# BatteryBoardV2B.net
KiCad netlist of a schematic drawn in EAGLE
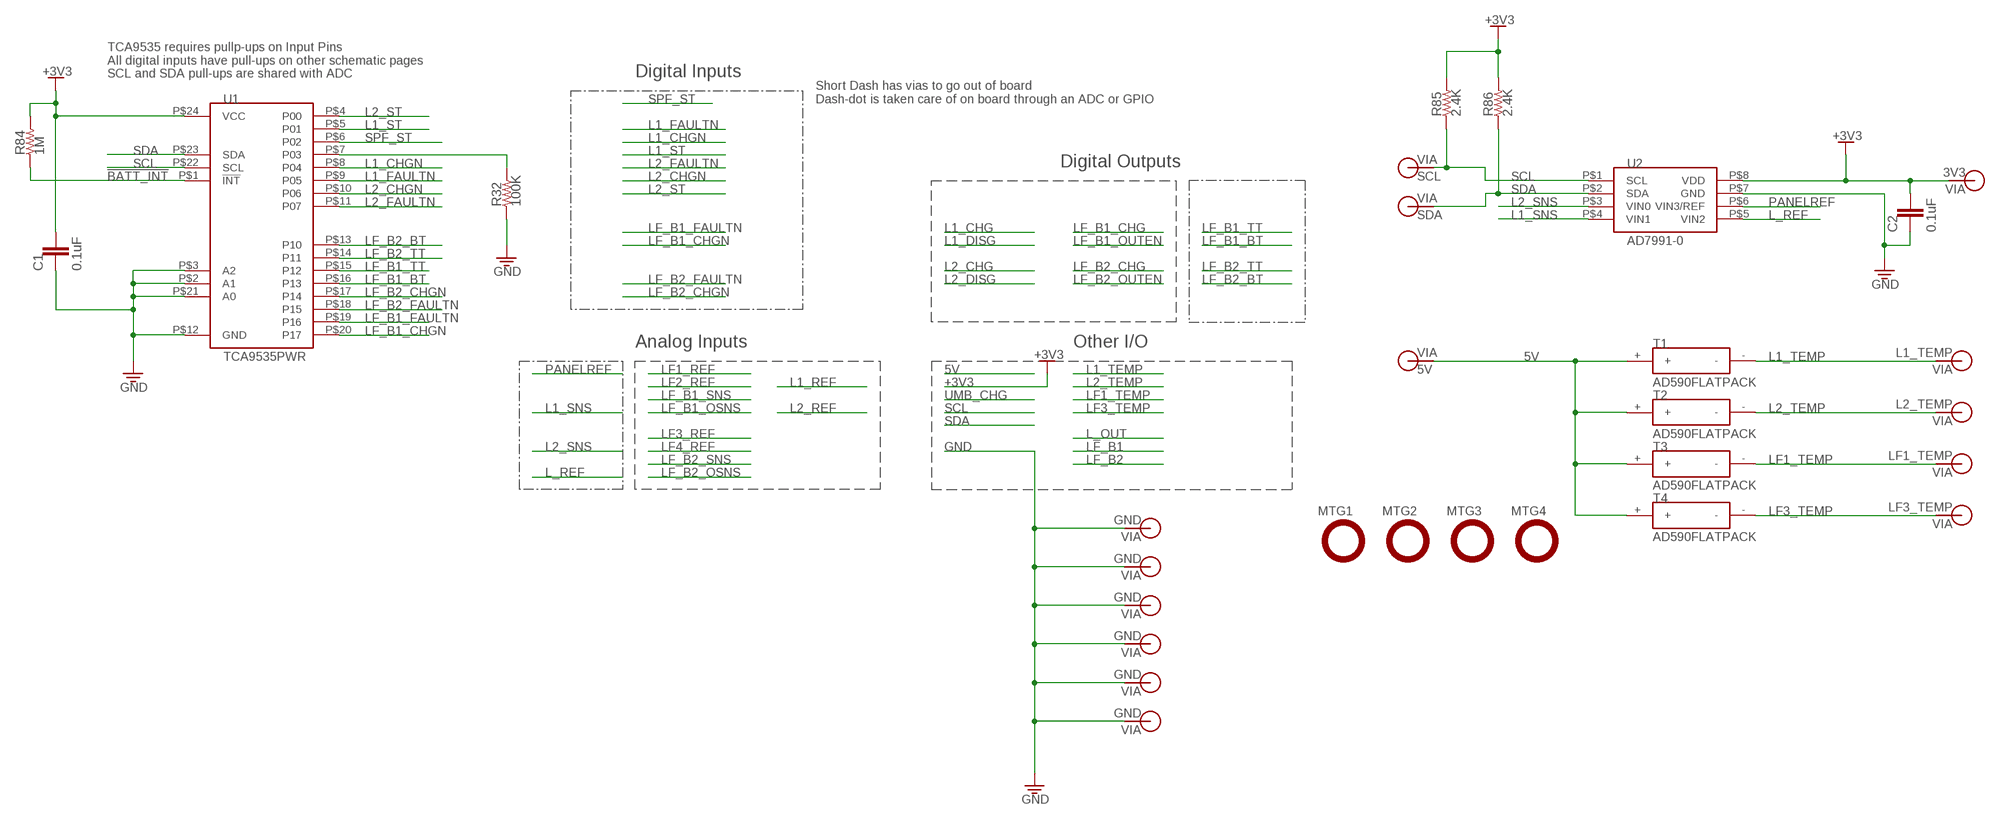
[diagram p0: schematic, sheet 1]
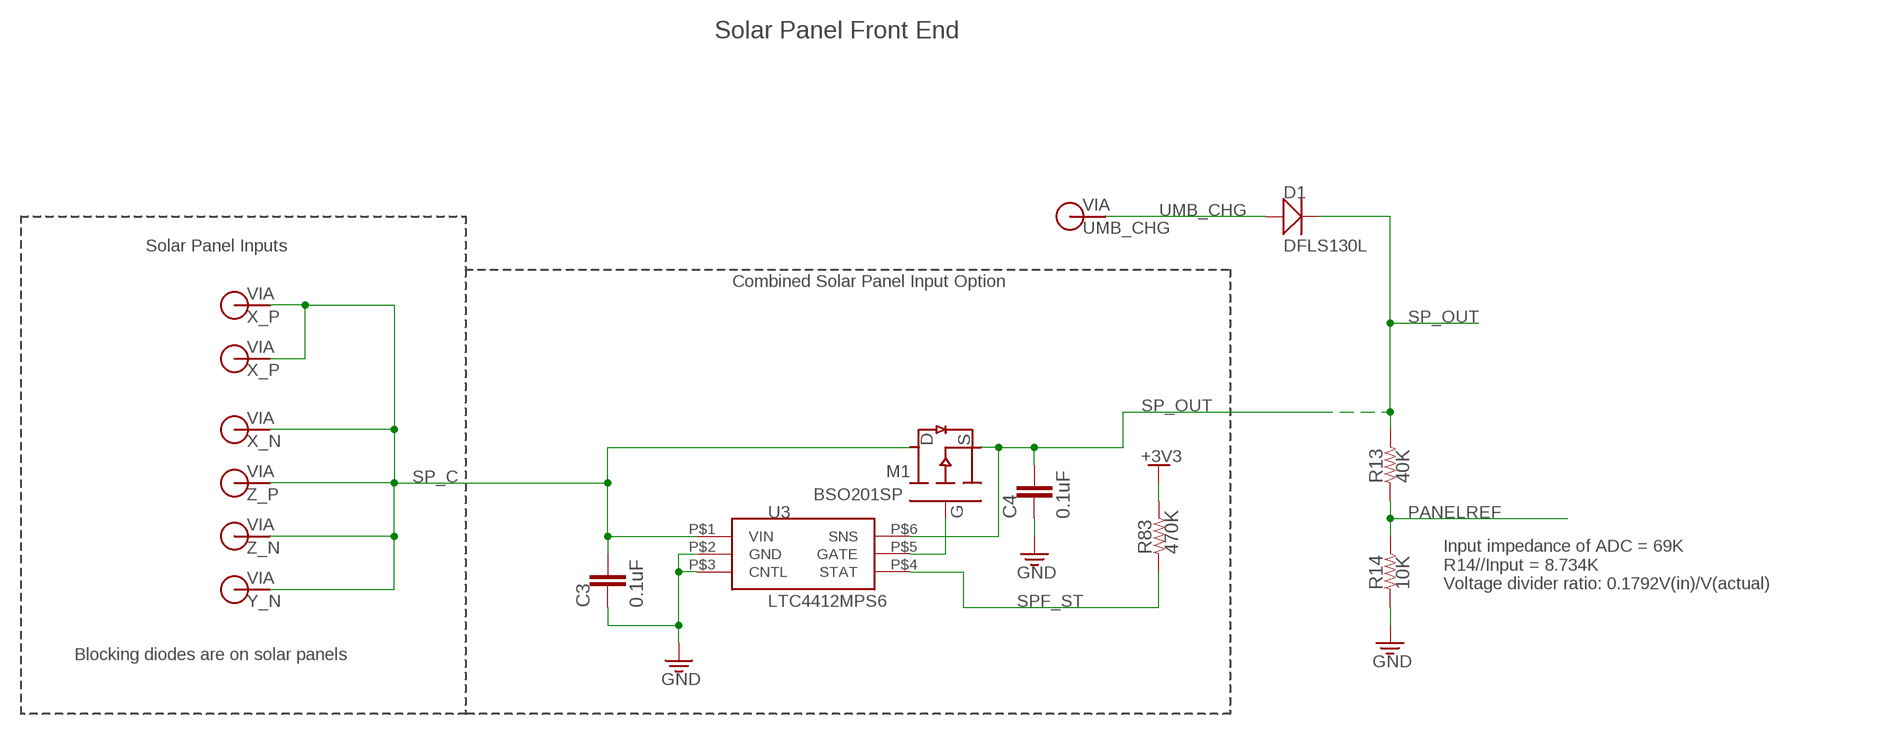
[diagram p1: schematic, sheet 2]
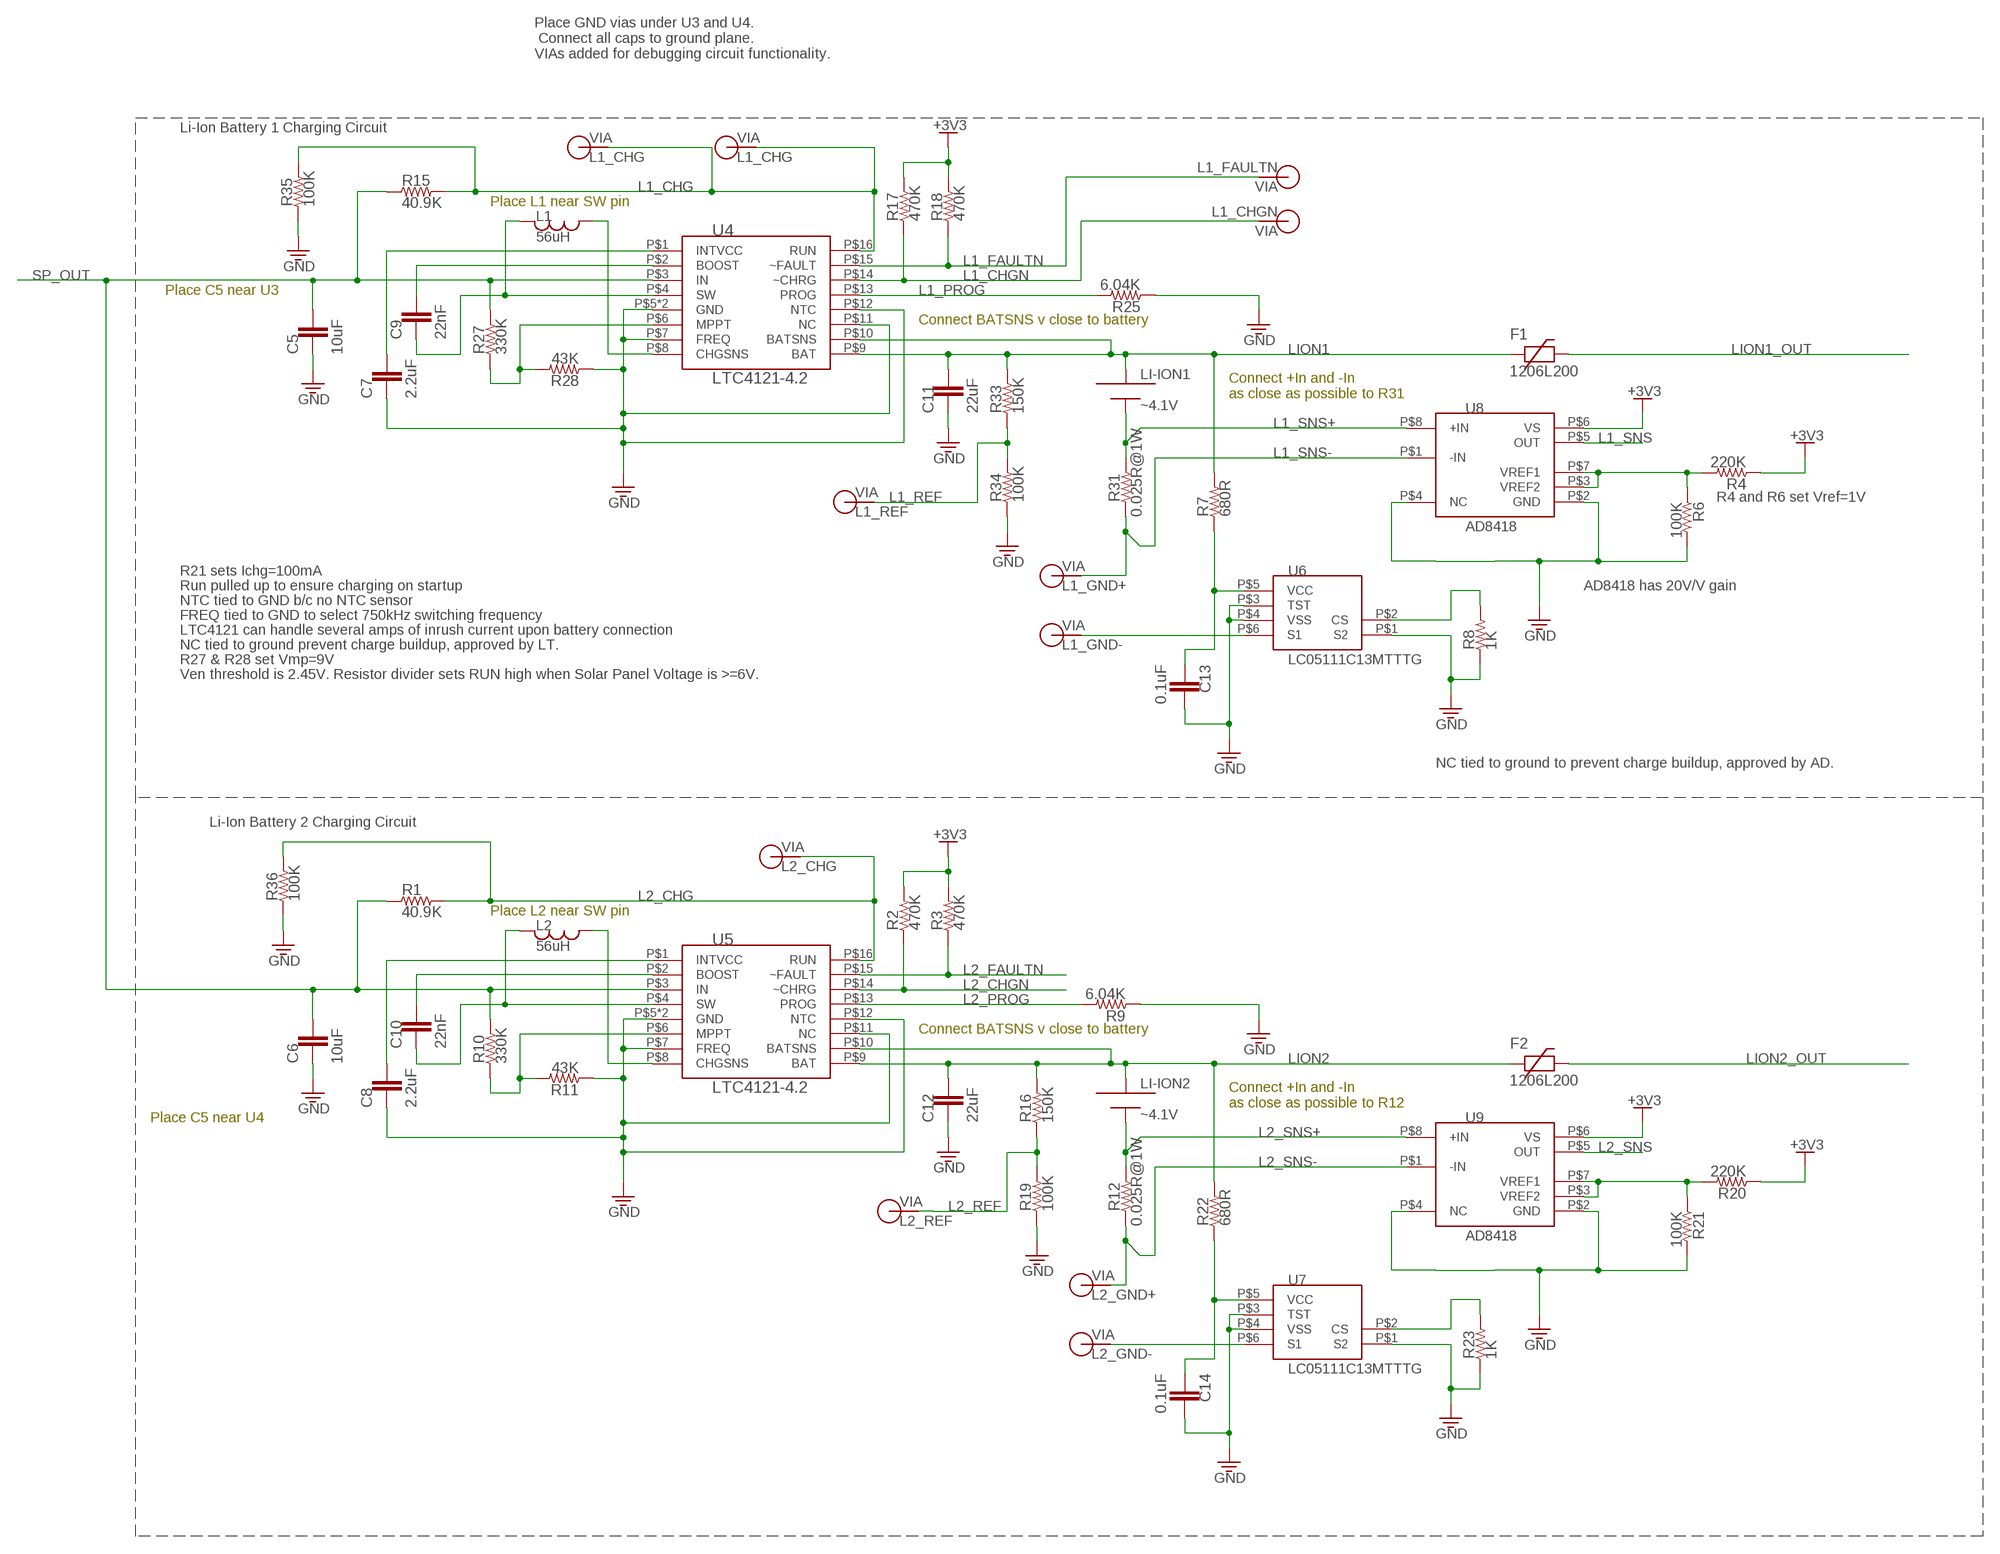
[diagram p2: schematic, sheet 3]
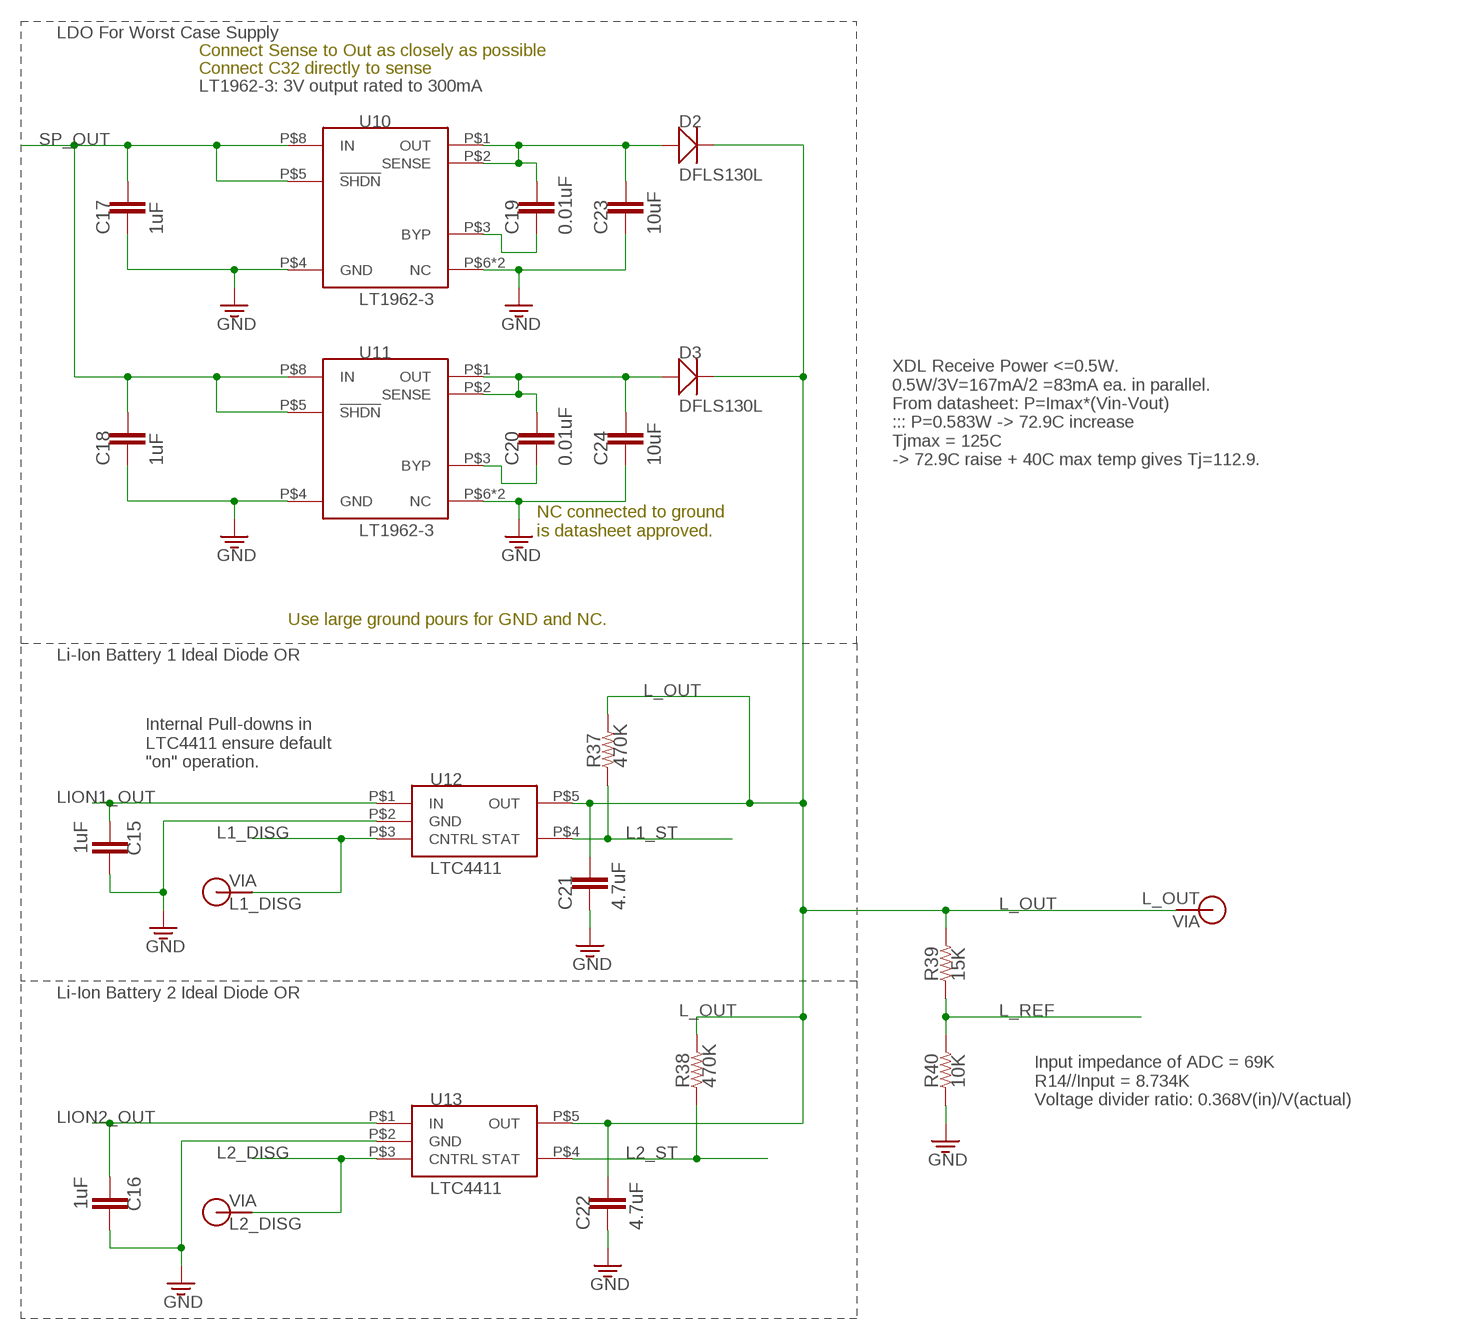
[diagram p3: schematic, sheet 4]
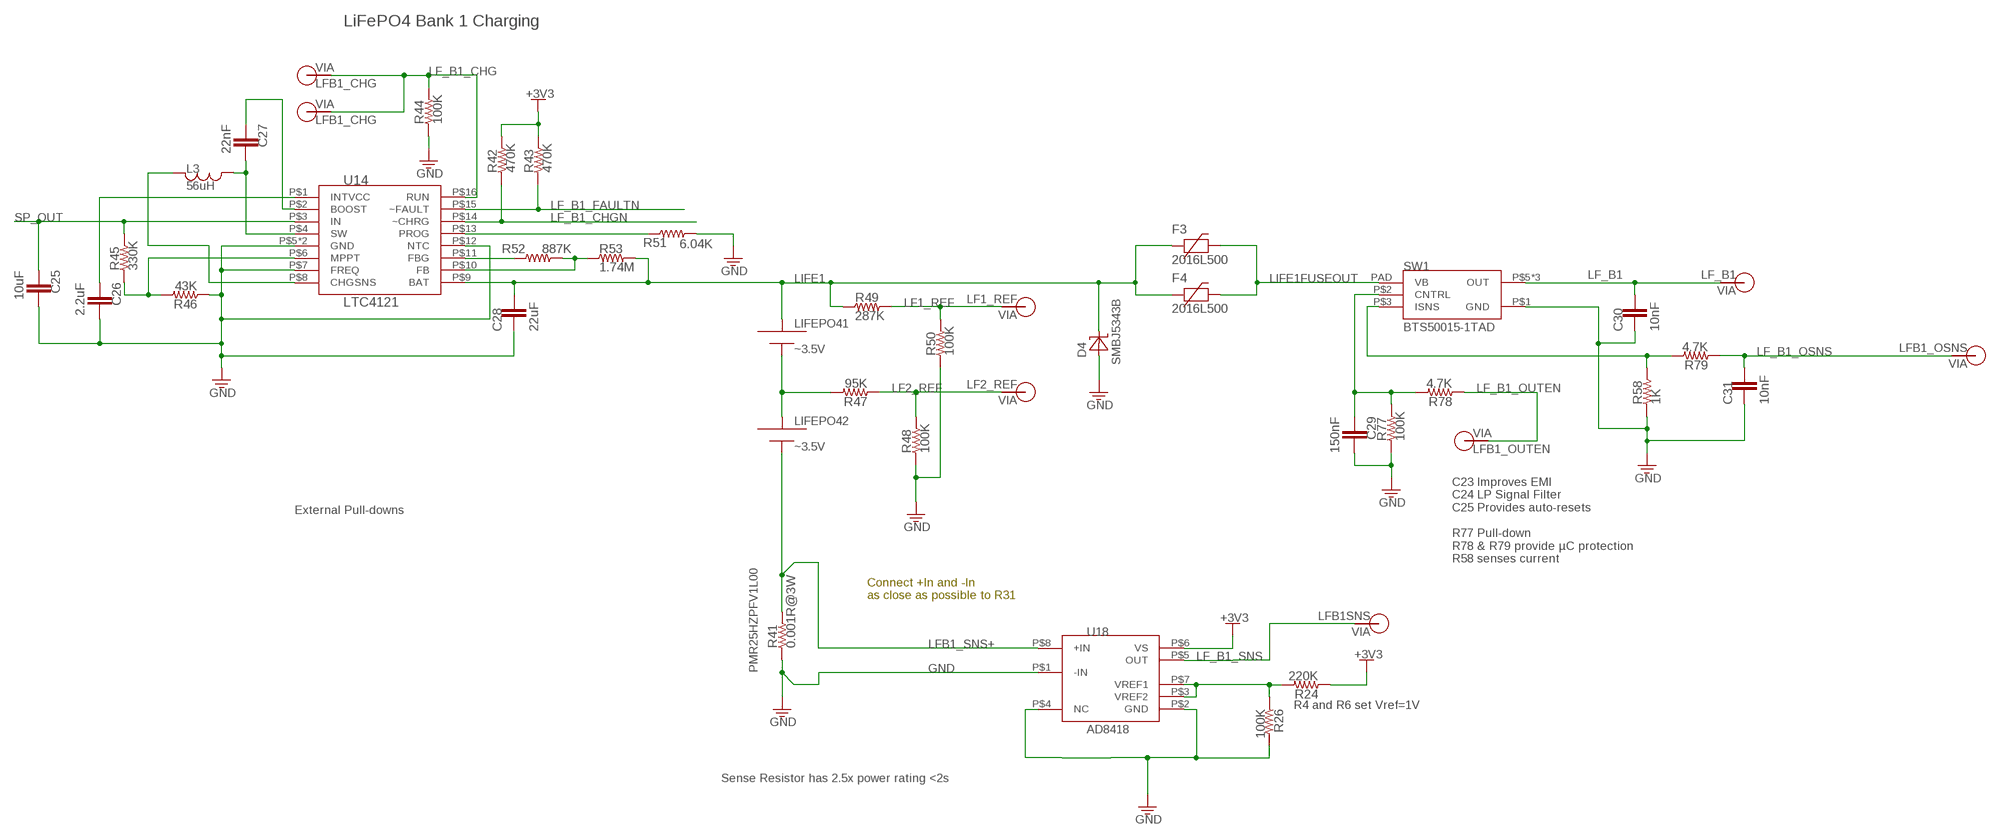
[diagram p4: schematic, sheet 5]
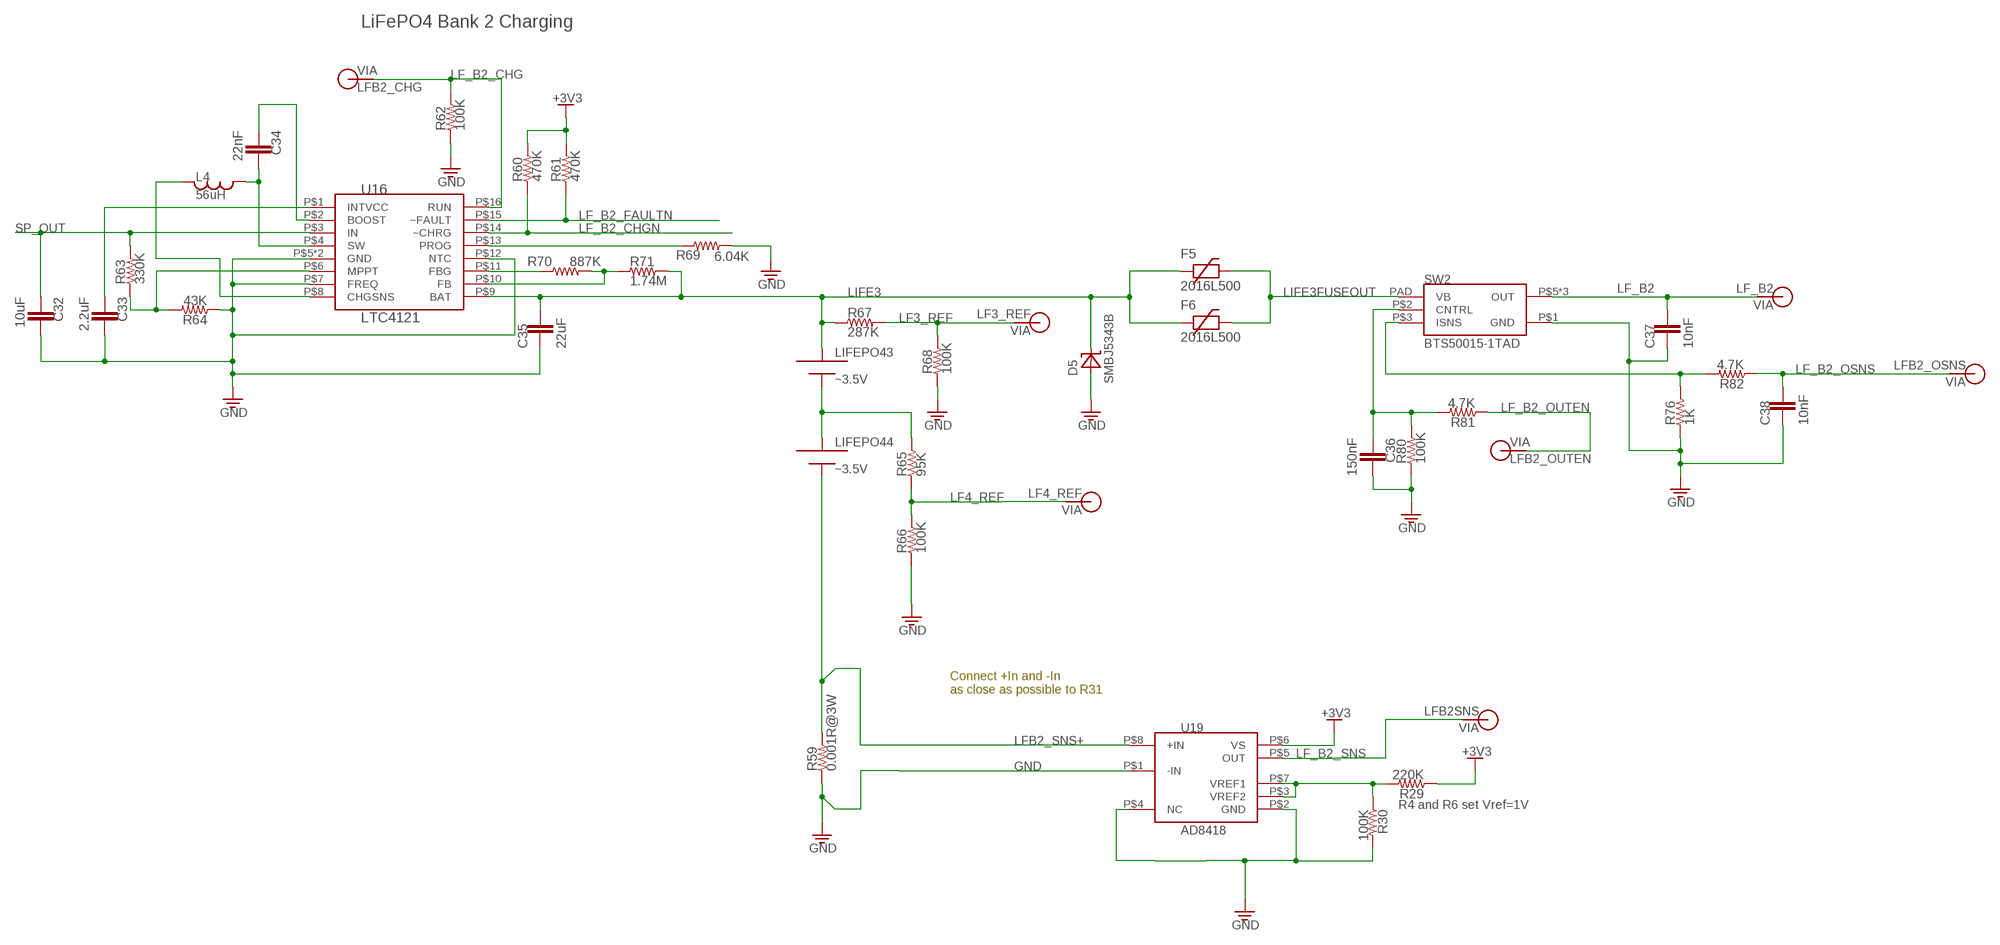
[diagram p5: schematic, sheet 6]

(export (version "E")
  (design (tool "Eeschema 10.0.6"))
  (components
    (comp (ref "C3")
      (value "0.1uF")
      (footprint "eagle-import:0805")
      (libsource (lib "eagle-import") (part "CAP0805"))
    )
    (comp (ref "C4")
      (value "0.1uF")
      (footprint "eagle-import:0805")
      (libsource (lib "eagle-import") (part "CAP0805"))
    )
    (comp (ref "D1")
      (value "DFLS130L")
      (footprint "eagle-import:PWRDI-123")
      (libsource (lib "eagle-import") (part "DFLS130L"))
    )
    (comp (ref "M1")
      (value "BSO201SP")
      (footprint "eagle-import:SO-8")
      (libsource (lib "eagle-import") (part "BSO201SP"))
    )
    (comp (ref "R13")
      (value "40K")
      (footprint "eagle-import:0805")
      (libsource (lib "eagle-import") (part "RES0805"))
    )
    (comp (ref "R14")
      (value "10K")
      (footprint "eagle-import:0805")
      (libsource (lib "eagle-import") (part "RES0805"))
    )
    (comp (ref "R83")
      (value "470K")
      (footprint "eagle-import:0805")
      (libsource (lib "eagle-import") (part "RES0805"))
    )
    (comp (ref "U3")
      (value "LTC4412MPS6")
      (footprint "eagle-import:TSOT23-6")
      (libsource (lib "eagle-import") (part "LTC4412"))
    )
    (comp (ref "V13")
      (value "X_P")
      (footprint "eagle-import:VIA-60MIL")
      (libsource (lib "eagle-import") (part "VIA-60MIL"))
    )
    (comp (ref "V14")
      (value "X_P")
      (footprint "eagle-import:VIA-60MIL-SQ")
      (libsource (lib "eagle-import") (part "VIA60MIL-SQ"))
    )
    (comp (ref "V15")
      (value "X_N")
      (footprint "eagle-import:VIA-60MIL")
      (libsource (lib "eagle-import") (part "VIA-60MIL"))
    )
    (comp (ref "V16")
      (value "Z_P")
      (footprint "eagle-import:VIA-60MIL")
      (libsource (lib "eagle-import") (part "VIA-60MIL"))
    )
    (comp (ref "V17")
      (value "Z_N")
      (footprint "eagle-import:VIA-60MIL")
      (libsource (lib "eagle-import") (part "VIA-60MIL"))
    )
    (comp (ref "V18")
      (value "Y_N")
      (footprint "eagle-import:VIA-60MIL")
      (libsource (lib "eagle-import") (part "VIA-60MIL"))
    )
    (comp (ref "V19")
      (value "UMB_CHG")
      (footprint "eagle-import:VIA-60MIL")
      (libsource (lib "eagle-import") (part "VIA-60MIL"))
    )
    (comp (ref "C25")
      (value "10uF")
      (footprint "eagle-import:0805")
      (libsource (lib "eagle-import") (part "CAP0805"))
    )
    (comp (ref "C26")
      (value "2.2uF")
      (footprint "eagle-import:0805")
      (libsource (lib "eagle-import") (part "CAP0805"))
    )
    (comp (ref "C27")
      (value "22nF")
      (footprint "eagle-import:0805")
      (libsource (lib "eagle-import") (part "CAP0805"))
    )
    (comp (ref "C28")
      (value "22uF")
      (footprint "eagle-import:0805")
      (libsource (lib "eagle-import") (part "CAP0805"))
    )
    (comp (ref "C29")
      (value "150nF")
      (footprint "eagle-import:0805")
      (libsource (lib "eagle-import") (part "CAP0805"))
    )
    (comp (ref "C30")
      (value "10nF")
      (footprint "eagle-import:0805")
      (libsource (lib "eagle-import") (part "CAP0805"))
    )
    (comp (ref "C31")
      (value "10nF")
      (footprint "eagle-import:0805")
      (libsource (lib "eagle-import") (part "CAP0805"))
    )
    (comp (ref "D4")
      (value "SMBJ5343B")
      (footprint "eagle-import:DO214AA")
      (libsource (lib "eagle-import") (part "SMBJ5343B"))
    )
    (comp (ref "F3")
      (value "2016L500")
      (footprint "eagle-import:2016")
      (libsource (lib "eagle-import") (part "2016L500"))
    )
    (comp (ref "F4")
      (value "2016L500")
      (footprint "eagle-import:2016")
      (libsource (lib "eagle-import") (part "2016L500"))
    )
    (comp (ref "L3")
      (value "56uH")
      (footprint "eagle-import:1812")
      (libsource (lib "eagle-import") (part "IND1812"))
    )
    (comp (ref "LIFEPO41")
      (value "~3.5V")
      (footprint "eagle-import:EQUISAT-BATTERY-VA")
      (libsource (lib "eagle-import") (part "LIFEPO4VA"))
    )
    (comp (ref "LIFEPO42")
      (value "~3.5V")
      (footprint "eagle-import:EQUISAT-BATTERY-VB")
      (libsource (lib "eagle-import") (part "LIFEPO4VB"))
    )
    (comp (ref "R24")
      (value "220K")
      (footprint "eagle-import:0805")
      (libsource (lib "eagle-import") (part "RES0805"))
    )
    (comp (ref "R26")
      (value "100K")
      (footprint "eagle-import:0805")
      (libsource (lib "eagle-import") (part "RES0805"))
    )
    (comp (ref "R41")
      (value "0.001R@3W")
      (footprint "eagle-import:1210")
      (libsource (lib "eagle-import") (part "RES1210"))
    )
    (comp (ref "R42")
      (value "470K")
      (footprint "eagle-import:0805")
      (libsource (lib "eagle-import") (part "RES0805"))
    )
    (comp (ref "R43")
      (value "470K")
      (footprint "eagle-import:0805")
      (libsource (lib "eagle-import") (part "RES0805"))
    )
    (comp (ref "R44")
      (value "100K")
      (footprint "eagle-import:0805")
      (libsource (lib "eagle-import") (part "RES0805"))
    )
    (comp (ref "R45")
      (value "330K")
      (footprint "eagle-import:0805")
      (libsource (lib "eagle-import") (part "RES0805"))
    )
    (comp (ref "R46")
      (value "43K")
      (footprint "eagle-import:0805")
      (libsource (lib "eagle-import") (part "RES0805"))
    )
    (comp (ref "R47")
      (value "95K")
      (footprint "eagle-import:0805")
      (libsource (lib "eagle-import") (part "RES0805"))
    )
    (comp (ref "R48")
      (value "100K")
      (footprint "eagle-import:0805")
      (libsource (lib "eagle-import") (part "RES0805"))
    )
    (comp (ref "R49")
      (value "287K")
      (footprint "eagle-import:0805")
      (libsource (lib "eagle-import") (part "RES0805"))
    )
    (comp (ref "R50")
      (value "100K")
      (footprint "eagle-import:0805")
      (libsource (lib "eagle-import") (part "RES0805"))
    )
    (comp (ref "R51")
      (value "6.04K")
      (footprint "eagle-import:0805")
      (libsource (lib "eagle-import") (part "RES0805"))
    )
    (comp (ref "R52")
      (value "887K")
      (footprint "eagle-import:0805")
      (libsource (lib "eagle-import") (part "RES0805"))
    )
    (comp (ref "R53")
      (value "1.74M")
      (footprint "eagle-import:0805")
      (libsource (lib "eagle-import") (part "RES0805"))
    )
    (comp (ref "R58")
      (value "1K")
      (footprint "eagle-import:0805")
      (libsource (lib "eagle-import") (part "RES0805"))
    )
    (comp (ref "R77")
      (value "100K")
      (footprint "eagle-import:0805")
      (libsource (lib "eagle-import") (part "RES0805"))
    )
    (comp (ref "R78")
      (value "4.7K")
      (footprint "eagle-import:0805")
      (libsource (lib "eagle-import") (part "RES0805"))
    )
    (comp (ref "R79")
      (value "4.7K")
      (footprint "eagle-import:0805")
      (libsource (lib "eagle-import") (part "RES0805"))
    )
    (comp (ref "SW1")
      (value "BTS50015-1TAD")
      (footprint "eagle-import:TO-263-7-8")
      (libsource (lib "eagle-import") (part "BTS50015-1TAD"))
    )
    (comp (ref "U14")
      (value "LTC4121")
      (footprint "eagle-import:QFN-16-PAD")
      (libsource (lib "eagle-import") (part "LTC4121"))
    )
    (comp (ref "U18")
      (value "AD8418")
      (footprint "eagle-import:MSOP-8")
      (libsource (lib "eagle-import") (part "AD8418"))
    )
    (comp (ref "V32")
      (value "LFB1_CHG")
      (footprint "eagle-import:VIA-60MIL-SQ")
      (libsource (lib "eagle-import") (part "VIA60MIL-SQ"))
    )
    (comp (ref "V35")
      (value "LFB1_CHG")
      (footprint "eagle-import:VIA-60MIL")
      (libsource (lib "eagle-import") (part "VIA-60MIL"))
    )
    (comp (ref "V40")
      (value "LFB1SNS")
      (footprint "eagle-import:VIA-60MIL")
      (libsource (lib "eagle-import") (part "VIA-60MIL"))
    )
    (comp (ref "V41")
      (value "LF1_REF")
      (footprint "eagle-import:VIA-60MIL")
      (libsource (lib "eagle-import") (part "VIA-60MIL"))
    )
    (comp (ref "V42")
      (value "LF2_REF")
      (footprint "eagle-import:VIA-60MIL")
      (libsource (lib "eagle-import") (part "VIA-60MIL"))
    )
    (comp (ref "V43")
      (value "LFB1_OUTEN")
      (footprint "eagle-import:VIA-60MIL")
      (libsource (lib "eagle-import") (part "VIA-60MIL"))
    )
    (comp (ref "V45")
      (value "LF_B1")
      (footprint "eagle-import:VIA-120MIL")
      (libsource (lib "eagle-import") (part "VIA-120MIL"))
    )
    (comp (ref "V46")
      (value "LFB1_OSNS")
      (footprint "eagle-import:VIA-60MIL")
      (libsource (lib "eagle-import") (part "VIA-60MIL"))
    )
    (comp (ref "C5")
      (value "10uF")
      (footprint "eagle-import:0805")
      (libsource (lib "eagle-import") (part "CAP0805"))
    )
    (comp (ref "C6")
      (value "10uF")
      (footprint "eagle-import:0805")
      (libsource (lib "eagle-import") (part "CAP0805"))
    )
    (comp (ref "C7")
      (value "2.2uF")
      (footprint "eagle-import:0805")
      (libsource (lib "eagle-import") (part "CAP0805"))
    )
    (comp (ref "C8")
      (value "2.2uF")
      (footprint "eagle-import:0805")
      (libsource (lib "eagle-import") (part "CAP0805"))
    )
    (comp (ref "C9")
      (value "22nF")
      (footprint "eagle-import:0805")
      (libsource (lib "eagle-import") (part "CAP0805"))
    )
    (comp (ref "C10")
      (value "22nF")
      (footprint "eagle-import:0805")
      (libsource (lib "eagle-import") (part "CAP0805"))
    )
    (comp (ref "C11")
      (value "22uF")
      (footprint "eagle-import:0805")
      (libsource (lib "eagle-import") (part "CAP0805"))
    )
    (comp (ref "C12")
      (value "22uF")
      (footprint "eagle-import:0805")
      (libsource (lib "eagle-import") (part "CAP0805"))
    )
    (comp (ref "C13")
      (value "0.1uF")
      (footprint "eagle-import:0805")
      (libsource (lib "eagle-import") (part "CAP0805"))
    )
    (comp (ref "C14")
      (value "0.1uF")
      (footprint "eagle-import:0805")
      (libsource (lib "eagle-import") (part "CAP0805"))
    )
    (comp (ref "F1")
      (value "1206L200")
      (footprint "eagle-import:1206")
      (libsource (lib "eagle-import") (part "PTCFUSE1206"))
    )
    (comp (ref "F2")
      (value "1206L200")
      (footprint "eagle-import:1206")
      (libsource (lib "eagle-import") (part "PTCFUSE1206"))
    )
    (comp (ref "L1")
      (value "56uH")
      (footprint "eagle-import:1812")
      (libsource (lib "eagle-import") (part "IND1812"))
    )
    (comp (ref "L2")
      (value "56uH")
      (footprint "eagle-import:1812")
      (libsource (lib "eagle-import") (part "IND1812"))
    )
    (comp (ref "LI-ION1")
      (value "~4.1V")
      (footprint "eagle-import:EQUISAT-BATTERY-VA")
      (libsource (lib "eagle-import") (part "LI-ION"))
    )
    (comp (ref "LI-ION2")
      (value "~4.1V")
      (footprint "eagle-import:EQUISAT-BATTERY-VA")
      (libsource (lib "eagle-import") (part "LI-ION"))
    )
    (comp (ref "R1")
      (value "40.9K")
      (footprint "eagle-import:0805")
      (libsource (lib "eagle-import") (part "RES0805"))
    )
    (comp (ref "R2")
      (value "470K")
      (footprint "eagle-import:0805")
      (libsource (lib "eagle-import") (part "RES0805"))
    )
    (comp (ref "R3")
      (value "470K")
      (footprint "eagle-import:0805")
      (libsource (lib "eagle-import") (part "RES0805"))
    )
    (comp (ref "R4")
      (value "220K")
      (footprint "eagle-import:0805")
      (libsource (lib "eagle-import") (part "RES0805"))
    )
    (comp (ref "R6")
      (value "100K")
      (footprint "eagle-import:0805")
      (libsource (lib "eagle-import") (part "RES0805"))
    )
    (comp (ref "R7")
      (value "680R")
      (footprint "eagle-import:0805")
      (libsource (lib "eagle-import") (part "RES0805"))
    )
    (comp (ref "R8")
      (value "1K")
      (footprint "eagle-import:0805")
      (libsource (lib "eagle-import") (part "RES0805"))
    )
    (comp (ref "R9")
      (value "6.04K")
      (footprint "eagle-import:0805")
      (libsource (lib "eagle-import") (part "RES0805"))
    )
    (comp (ref "R10")
      (value "330K")
      (footprint "eagle-import:0805")
      (libsource (lib "eagle-import") (part "RES0805"))
    )
    (comp (ref "R11")
      (value "43K")
      (footprint "eagle-import:0805")
      (libsource (lib "eagle-import") (part "RES0805"))
    )
    (comp (ref "R12")
      (value "0.025R@1W")
      (footprint "eagle-import:1210")
      (libsource (lib "eagle-import") (part "RES1210"))
    )
    (comp (ref "R15")
      (value "40.9K")
      (footprint "eagle-import:0805")
      (libsource (lib "eagle-import") (part "RES0805"))
    )
    (comp (ref "R16")
      (value "150K")
      (footprint "eagle-import:0805")
      (libsource (lib "eagle-import") (part "RES0805"))
    )
    (comp (ref "R17")
      (value "470K")
      (footprint "eagle-import:0805")
      (libsource (lib "eagle-import") (part "RES0805"))
    )
    (comp (ref "R18")
      (value "470K")
      (footprint "eagle-import:0805")
      (libsource (lib "eagle-import") (part "RES0805"))
    )
    (comp (ref "R19")
      (value "100K")
      (footprint "eagle-import:0805")
      (libsource (lib "eagle-import") (part "RES0805"))
    )
    (comp (ref "R20")
      (value "220K")
      (footprint "eagle-import:0805")
      (libsource (lib "eagle-import") (part "RES0805"))
    )
    (comp (ref "R21")
      (value "100K")
      (footprint "eagle-import:0805")
      (libsource (lib "eagle-import") (part "RES0805"))
    )
    (comp (ref "R22")
      (value "680R")
      (footprint "eagle-import:0805")
      (libsource (lib "eagle-import") (part "RES0805"))
    )
    (comp (ref "R23")
      (value "1K")
      (footprint "eagle-import:0805")
      (libsource (lib "eagle-import") (part "RES0805"))
    )
    (comp (ref "R25")
      (value "6.04K")
      (footprint "eagle-import:0805")
      (libsource (lib "eagle-import") (part "RES0805"))
    )
    (comp (ref "R27")
      (value "330K")
      (footprint "eagle-import:0805")
      (libsource (lib "eagle-import") (part "RES0805"))
    )
    (comp (ref "R28")
      (value "43K")
      (footprint "eagle-import:0805")
      (libsource (lib "eagle-import") (part "RES0805"))
    )
    (comp (ref "R31")
      (value "0.025R@1W")
      (footprint "eagle-import:1210")
      (libsource (lib "eagle-import") (part "RES1210"))
    )
    (comp (ref "R33")
      (value "150K")
      (footprint "eagle-import:0805")
      (libsource (lib "eagle-import") (part "RES0805"))
    )
    (comp (ref "R34")
      (value "100K")
      (footprint "eagle-import:0805")
      (libsource (lib "eagle-import") (part "RES0805"))
    )
    (comp (ref "R35")
      (value "100K")
      (footprint "eagle-import:0805")
      (libsource (lib "eagle-import") (part "RES0805"))
    )
    (comp (ref "R36")
      (value "100K")
      (footprint "eagle-import:0805")
      (libsource (lib "eagle-import") (part "RES0805"))
    )
    (comp (ref "U4")
      (value "LTC4121-4.2")
      (footprint "eagle-import:QFN-16-PAD")
      (libsource (lib "eagle-import") (part "LTC4121-4.2"))
    )
    (comp (ref "U5")
      (value "LTC4121-4.2")
      (footprint "eagle-import:QFN-16-PAD")
      (libsource (lib "eagle-import") (part "LTC4121-4.2"))
    )
    (comp (ref "U6")
      (value "LC05111C13MTTTG")
      (footprint "eagle-import:WDFN6")
      (libsource (lib "eagle-import") (part "LC05111C13MTTTG"))
    )
    (comp (ref "U7")
      (value "LC05111C13MTTTG")
      (footprint "eagle-import:WDFN6")
      (libsource (lib "eagle-import") (part "LC05111C13MTTTG"))
    )
    (comp (ref "U8")
      (value "AD8418")
      (footprint "eagle-import:MSOP-8")
      (libsource (lib "eagle-import") (part "AD8418"))
    )
    (comp (ref "U9")
      (value "AD8418")
      (footprint "eagle-import:MSOP-8")
      (libsource (lib "eagle-import") (part "AD8418"))
    )
    (comp (ref "V20")
      (value "L1_CHG")
      (footprint "eagle-import:VIA-60MIL")
      (libsource (lib "eagle-import") (part "VIA-60MIL"))
    )
    (comp (ref "V21")
      (value "L1_REF")
      (footprint "eagle-import:VIA-60MIL")
      (libsource (lib "eagle-import") (part "VIA-60MIL"))
    )
    (comp (ref "V22")
      (value "L1_GND+")
      (footprint "eagle-import:VIA-60MIL")
      (libsource (lib "eagle-import") (part "VIA-60MIL"))
    )
    (comp (ref "V23")
      (value "L1_GND-")
      (footprint "eagle-import:VIA-60MIL")
      (libsource (lib "eagle-import") (part "VIA-60MIL"))
    )
    (comp (ref "V24")
      (value "L2_GND+")
      (footprint "eagle-import:VIA-60MIL")
      (libsource (lib "eagle-import") (part "VIA-60MIL"))
    )
    (comp (ref "V25")
      (value "L2_GND-")
      (footprint "eagle-import:VIA-60MIL")
      (libsource (lib "eagle-import") (part "VIA-60MIL"))
    )
    (comp (ref "V26")
      (value "L1_FAULTN")
      (footprint "eagle-import:VIA-60MIL-SQ")
      (libsource (lib "eagle-import") (part "VIA60MIL-SQ"))
    )
    (comp (ref "V27")
      (value "L1_CHGN")
      (footprint "eagle-import:VIA-60MIL-SQ")
      (libsource (lib "eagle-import") (part "VIA60MIL-SQ"))
    )
    (comp (ref "V31")
      (value "L2_REF")
      (footprint "eagle-import:VIA-60MIL")
      (libsource (lib "eagle-import") (part "VIA-60MIL"))
    )
    (comp (ref "V33")
      (value "L2_CHG")
      (footprint "eagle-import:VIA-60MIL")
      (libsource (lib "eagle-import") (part "VIA-60MIL"))
    )
    (comp (ref "V48")
      (value "L1_CHG")
      (footprint "eagle-import:VIA-60MIL-SQ")
      (libsource (lib "eagle-import") (part "VIA60MIL-SQ"))
    )
    (comp (ref "C15")
      (value "1uF")
      (footprint "eagle-import:0805")
      (libsource (lib "eagle-import") (part "CAP0805"))
    )
    (comp (ref "C16")
      (value "1uF")
      (footprint "eagle-import:0805")
      (libsource (lib "eagle-import") (part "CAP0805"))
    )
    (comp (ref "C17")
      (value "1uF")
      (footprint "eagle-import:0805")
      (libsource (lib "eagle-import") (part "CAP0805"))
    )
    (comp (ref "C18")
      (value "1uF")
      (footprint "eagle-import:0805")
      (libsource (lib "eagle-import") (part "CAP0805"))
    )
    (comp (ref "C19")
      (value "0.01uF")
      (footprint "eagle-import:0805")
      (libsource (lib "eagle-import") (part "CAP0805"))
    )
    (comp (ref "C20")
      (value "0.01uF")
      (footprint "eagle-import:0805")
      (libsource (lib "eagle-import") (part "CAP0805"))
    )
    (comp (ref "C21")
      (value "4.7uF")
      (footprint "eagle-import:0805")
      (libsource (lib "eagle-import") (part "CAP0805"))
    )
    (comp (ref "C22")
      (value "4.7uF")
      (footprint "eagle-import:0805")
      (libsource (lib "eagle-import") (part "CAP0805"))
    )
    (comp (ref "C23")
      (value "10uF")
      (footprint "eagle-import:0805")
      (libsource (lib "eagle-import") (part "CAP0805"))
    )
    (comp (ref "C24")
      (value "10uF")
      (footprint "eagle-import:0805")
      (libsource (lib "eagle-import") (part "CAP0805"))
    )
    (comp (ref "D2")
      (value "DFLS130L")
      (footprint "eagle-import:PWRDI-123")
      (libsource (lib "eagle-import") (part "DFLS130L"))
    )
    (comp (ref "D3")
      (value "DFLS130L")
      (footprint "eagle-import:PWRDI-123")
      (libsource (lib "eagle-import") (part "DFLS130L"))
    )
    (comp (ref "R37")
      (value "470K")
      (footprint "eagle-import:0805")
      (libsource (lib "eagle-import") (part "RES0805"))
    )
    (comp (ref "R38")
      (value "470K")
      (footprint "eagle-import:0805")
      (libsource (lib "eagle-import") (part "RES0805"))
    )
    (comp (ref "R39")
      (value "15K")
      (footprint "eagle-import:0805")
      (libsource (lib "eagle-import") (part "RES0805"))
    )
    (comp (ref "R40")
      (value "10K")
      (footprint "eagle-import:0805")
      (libsource (lib "eagle-import") (part "RES0805"))
    )
    (comp (ref "U10")
      (value "LT1962-3")
      (footprint "eagle-import:MSOP-8")
      (libsource (lib "eagle-import") (part "LT1962-3"))
    )
    (comp (ref "U11")
      (value "LT1962-3")
      (footprint "eagle-import:MSOP-8")
      (libsource (lib "eagle-import") (part "LT1962-3"))
    )
    (comp (ref "U12")
      (value "LTC4411")
      (footprint "eagle-import:TSOT23-5")
      (libsource (lib "eagle-import") (part "LTC4411"))
    )
    (comp (ref "U13")
      (value "LTC4411")
      (footprint "eagle-import:TSOT23-5")
      (libsource (lib "eagle-import") (part "LTC4411"))
    )
    (comp (ref "V29")
      (value "L1_DISG")
      (footprint "eagle-import:VIA-60MIL")
      (libsource (lib "eagle-import") (part "VIA-60MIL"))
    )
    (comp (ref "V30")
      (value "L2_DISG")
      (footprint "eagle-import:VIA-60MIL")
      (libsource (lib "eagle-import") (part "VIA-60MIL"))
    )
    (comp (ref "V34")
      (value "L_OUT")
      (footprint "eagle-import:VIA-120MIL")
      (libsource (lib "eagle-import") (part "VIA-120MIL"))
    )
    (comp (ref "C32")
      (value "10uF")
      (footprint "eagle-import:0805")
      (libsource (lib "eagle-import") (part "CAP0805"))
    )
    (comp (ref "C33")
      (value "2.2uF")
      (footprint "eagle-import:0805")
      (libsource (lib "eagle-import") (part "CAP0805"))
    )
    (comp (ref "C34")
      (value "22nF")
      (footprint "eagle-import:0805")
      (libsource (lib "eagle-import") (part "CAP0805"))
    )
    (comp (ref "C35")
      (value "22uF")
      (footprint "eagle-import:0805")
      (libsource (lib "eagle-import") (part "CAP0805"))
    )
    (comp (ref "C36")
      (value "150nF")
      (footprint "eagle-import:0805")
      (libsource (lib "eagle-import") (part "CAP0805"))
    )
    (comp (ref "C37")
      (value "10nF")
      (footprint "eagle-import:0805")
      (libsource (lib "eagle-import") (part "CAP0805"))
    )
    (comp (ref "C38")
      (value "10nF")
      (footprint "eagle-import:0805")
      (libsource (lib "eagle-import") (part "CAP0805"))
    )
    (comp (ref "D5")
      (value "SMBJ5343B")
      (footprint "eagle-import:DO214AA")
      (libsource (lib "eagle-import") (part "SMBJ5343B"))
    )
    (comp (ref "F5")
      (value "2016L500")
      (footprint "eagle-import:2016")
      (libsource (lib "eagle-import") (part "2016L500"))
    )
    (comp (ref "F6")
      (value "2016L500")
      (footprint "eagle-import:2016")
      (libsource (lib "eagle-import") (part "2016L500"))
    )
    (comp (ref "L4")
      (value "56uH")
      (footprint "eagle-import:1812")
      (libsource (lib "eagle-import") (part "IND1812"))
    )
    (comp (ref "LIFEPO43")
      (value "~3.5V")
      (footprint "eagle-import:EQUISAT-BATTERY-VA")
      (libsource (lib "eagle-import") (part "LIFEPO4VA"))
    )
    (comp (ref "LIFEPO44")
      (value "~3.5V")
      (footprint "eagle-import:EQUISAT-BATTERY-VB")
      (libsource (lib "eagle-import") (part "LIFEPO4VB"))
    )
    (comp (ref "R29")
      (value "220K")
      (footprint "eagle-import:0805")
      (libsource (lib "eagle-import") (part "RES0805"))
    )
    (comp (ref "R30")
      (value "100K")
      (footprint "eagle-import:0805")
      (libsource (lib "eagle-import") (part "RES0805"))
    )
    (comp (ref "R59")
      (value "0.001R@3W")
      (footprint "eagle-import:1210")
      (libsource (lib "eagle-import") (part "RES1210"))
    )
    (comp (ref "R60")
      (value "470K")
      (footprint "eagle-import:0805")
      (libsource (lib "eagle-import") (part "RES0805"))
    )
    (comp (ref "R61")
      (value "470K")
      (footprint "eagle-import:0805")
      (libsource (lib "eagle-import") (part "RES0805"))
    )
    (comp (ref "R62")
      (value "100K")
      (footprint "eagle-import:0805")
      (libsource (lib "eagle-import") (part "RES0805"))
    )
    (comp (ref "R63")
      (value "330K")
      (footprint "eagle-import:0805")
      (libsource (lib "eagle-import") (part "RES0805"))
    )
    (comp (ref "R64")
      (value "43K")
      (footprint "eagle-import:0805")
      (libsource (lib "eagle-import") (part "RES0805"))
    )
    (comp (ref "R65")
      (value "95K")
      (footprint "eagle-import:0805")
      (libsource (lib "eagle-import") (part "RES0805"))
    )
    (comp (ref "R66")
      (value "100K")
      (footprint "eagle-import:0805")
      (libsource (lib "eagle-import") (part "RES0805"))
    )
    (comp (ref "R67")
      (value "287K")
      (footprint "eagle-import:0805")
      (libsource (lib "eagle-import") (part "RES0805"))
    )
    (comp (ref "R68")
      (value "100K")
      (footprint "eagle-import:0805")
      (libsource (lib "eagle-import") (part "RES0805"))
    )
    (comp (ref "R69")
      (value "6.04K")
      (footprint "eagle-import:0805")
      (libsource (lib "eagle-import") (part "RES0805"))
    )
    (comp (ref "R70")
      (value "887K")
      (footprint "eagle-import:0805")
      (libsource (lib "eagle-import") (part "RES0805"))
    )
    (comp (ref "R71")
      (value "1.74M")
      (footprint "eagle-import:0805")
      (libsource (lib "eagle-import") (part "RES0805"))
    )
    (comp (ref "R76")
      (value "1K")
      (footprint "eagle-import:0805")
      (libsource (lib "eagle-import") (part "RES0805"))
    )
    (comp (ref "R80")
      (value "100K")
      (footprint "eagle-import:0805")
      (libsource (lib "eagle-import") (part "RES0805"))
    )
    (comp (ref "R81")
      (value "4.7K")
      (footprint "eagle-import:0805")
      (libsource (lib "eagle-import") (part "RES0805"))
    )
    (comp (ref "R82")
      (value "4.7K")
      (footprint "eagle-import:0805")
      (libsource (lib "eagle-import") (part "RES0805"))
    )
    (comp (ref "SW2")
      (value "BTS50015-1TAD")
      (footprint "eagle-import:TO-263-7-8")
      (libsource (lib "eagle-import") (part "BTS50015-1TAD"))
    )
    (comp (ref "U16")
      (value "LTC4121")
      (footprint "eagle-import:QFN-16-PAD")
      (libsource (lib "eagle-import") (part "LTC4121"))
    )
    (comp (ref "U19")
      (value "AD8418")
      (footprint "eagle-import:MSOP-8")
      (libsource (lib "eagle-import") (part "AD8418"))
    )
    (comp (ref "V44")
      (value "LFB2SNS")
      (footprint "eagle-import:VIA-60MIL")
      (libsource (lib "eagle-import") (part "VIA-60MIL"))
    )
    (comp (ref "V47")
      (value "LFB2_CHG")
      (footprint "eagle-import:VIA-60MIL")
      (libsource (lib "eagle-import") (part "VIA-60MIL"))
    )
    (comp (ref "V49")
      (value "LF3_REF")
      (footprint "eagle-import:VIA-60MIL")
      (libsource (lib "eagle-import") (part "VIA-60MIL"))
    )
    (comp (ref "V50")
      (value "LF4_REF")
      (footprint "eagle-import:VIA-60MIL")
      (libsource (lib "eagle-import") (part "VIA-60MIL"))
    )
    (comp (ref "V51")
      (value "LFB2_OUTEN")
      (footprint "eagle-import:VIA-60MIL")
      (libsource (lib "eagle-import") (part "VIA-60MIL"))
    )
    (comp (ref "V53")
      (value "LF_B2")
      (footprint "eagle-import:VIA-120MIL")
      (libsource (lib "eagle-import") (part "VIA-120MIL"))
    )
    (comp (ref "V99")
      (value "LFB2_OSNS")
      (footprint "eagle-import:VIA-60MIL")
      (libsource (lib "eagle-import") (part "VIA-60MIL"))
    )
    (comp (ref "C1")
      (value "0.1uF")
      (footprint "eagle-import:0805")
      (libsource (lib "eagle-import") (part "CAP0805"))
    )
    (comp (ref "C2")
      (value "0.1uF")
      (footprint "eagle-import:0805")
      (libsource (lib "eagle-import") (part "CAP0805"))
    )
    (comp (ref "MTG1")
      (value "MTG-NPTH-#2-CLOSE")
      (footprint "eagle-import:#2-CLOSE-NPTH")
      (libsource (lib "eagle-import") (part "MTG-NPTH-#2-CLOSE"))
    )
    (comp (ref "MTG2")
      (value "MTG-NPTH-#2-CLOSE")
      (footprint "eagle-import:#2-CLOSE-NPTH")
      (libsource (lib "eagle-import") (part "MTG-NPTH-#2-CLOSE"))
    )
    (comp (ref "MTG3")
      (value "MTG-NPTH-#2-CLOSE")
      (footprint "eagle-import:#2-CLOSE-NPTH")
      (libsource (lib "eagle-import") (part "MTG-NPTH-#2-CLOSE"))
    )
    (comp (ref "MTG4")
      (value "MTG-NPTH-#2-CLOSE")
      (footprint "eagle-import:#2-CLOSE-NPTH")
      (libsource (lib "eagle-import") (part "MTG-NPTH-#2-CLOSE"))
    )
    (comp (ref "R32")
      (value "100K")
      (footprint "eagle-import:0805")
      (libsource (lib "eagle-import") (part "RES0805"))
    )
    (comp (ref "R84")
      (value "1M")
      (footprint "eagle-import:0805")
      (libsource (lib "eagle-import") (part "RES0805"))
    )
    (comp (ref "R85")
      (value "2.4K")
      (footprint "eagle-import:0805")
      (libsource (lib "eagle-import") (part "RES0805"))
    )
    (comp (ref "R86")
      (value "2.4K")
      (footprint "eagle-import:0805")
      (libsource (lib "eagle-import") (part "RES0805"))
    )
    (comp (ref "T1")
      (value "AD590FLATPACK")
      (footprint "eagle-import:FLATPACK")
      (libsource (lib "eagle-import") (part "AD590FLATPACK"))
    )
    (comp (ref "T2")
      (value "AD590FLATPACK")
      (footprint "eagle-import:FLATPACK")
      (libsource (lib "eagle-import") (part "AD590FLATPACK"))
    )
    (comp (ref "T3")
      (value "AD590FLATPACK")
      (footprint "eagle-import:FLATPACK")
      (libsource (lib "eagle-import") (part "AD590FLATPACK"))
    )
    (comp (ref "T4")
      (value "AD590FLATPACK")
      (footprint "eagle-import:FLATPACK")
      (libsource (lib "eagle-import") (part "AD590FLATPACK"))
    )
    (comp (ref "U1")
      (value "TCA9535PWR")
      (footprint "eagle-import:TSSOP-24")
      (libsource (lib "eagle-import") (part "TCA9535PWR"))
    )
    (comp (ref "U2")
      (value "AD7991-0")
      (footprint "eagle-import:SOT-23-8")
      (libsource (lib "eagle-import") (part "AD7991-0"))
    )
    (comp (ref "V1")
      (value "GND")
      (footprint "eagle-import:VIA-120MIL")
      (libsource (lib "eagle-import") (part "VIA-120MIL"))
    )
    (comp (ref "V2")
      (value "GND")
      (footprint "eagle-import:VIA-120MIL")
      (libsource (lib "eagle-import") (part "VIA-120MIL"))
    )
    (comp (ref "V3")
      (value "GND")
      (footprint "eagle-import:VIA-60MIL-SQ")
      (libsource (lib "eagle-import") (part "VIA60MIL-SQ"))
    )
    (comp (ref "V4")
      (value "GND")
      (footprint "eagle-import:VIA-120MIL")
      (libsource (lib "eagle-import") (part "VIA-120MIL"))
    )
    (comp (ref "V5")
      (value "SCL")
      (footprint "eagle-import:VIA-60MIL")
      (libsource (lib "eagle-import") (part "VIA-60MIL"))
    )
    (comp (ref "V6")
      (value "SDA")
      (footprint "eagle-import:VIA-60MIL")
      (libsource (lib "eagle-import") (part "VIA-60MIL"))
    )
    (comp (ref "V7")
      (value "5V")
      (footprint "eagle-import:VIA-60MIL")
      (libsource (lib "eagle-import") (part "VIA-60MIL"))
    )
    (comp (ref "V8")
      (value "L1_TEMP")
      (footprint "eagle-import:VIA-60MIL")
      (libsource (lib "eagle-import") (part "VIA-60MIL"))
    )
    (comp (ref "V9")
      (value "L2_TEMP")
      (footprint "eagle-import:VIA-60MIL")
      (libsource (lib "eagle-import") (part "VIA-60MIL"))
    )
    (comp (ref "V10")
      (value "LF1_TEMP")
      (footprint "eagle-import:VIA-60MIL")
      (libsource (lib "eagle-import") (part "VIA-60MIL"))
    )
    (comp (ref "V11")
      (value "LF3_TEMP")
      (footprint "eagle-import:VIA-60MIL")
      (libsource (lib "eagle-import") (part "VIA-60MIL"))
    )
    (comp (ref "V12")
      (value "3V3")
      (footprint "eagle-import:VIA-60MIL")
      (libsource (lib "eagle-import") (part "VIA-60MIL"))
    )
    (comp (ref "V28")
      (value "GND")
      (footprint "eagle-import:VIA-60MIL-SQ")
      (libsource (lib "eagle-import") (part "VIA60MIL-SQ"))
    )
    (comp (ref "V36")
      (value "GND")
      (footprint "eagle-import:VIA-60MIL-SQ")
      (libsource (lib "eagle-import") (part "VIA60MIL-SQ"))
    )
  )
  (nets
    (net (code "1") (name "+3V3") (class "Default")
      (node (ref "C1") (pin "1") (pinfunction "P$1_1") (pintype "passive"))
      (node (ref "C2") (pin "1") (pinfunction "P$1_1") (pintype "passive"))
      (node (ref "R17") (pin "2") (pinfunction "2_2") (pintype "passive"))
      (node (ref "R18") (pin "2") (pinfunction "2_2") (pintype "passive"))
      (node (ref "R2") (pin "2") (pinfunction "2_2") (pintype "passive"))
      (node (ref "R20") (pin "1") (pinfunction "1_1") (pintype "passive"))
      (node (ref "R24") (pin "1") (pinfunction "1_1") (pintype "passive"))
      (node (ref "R29") (pin "1") (pinfunction "1_1") (pintype "passive"))
      (node (ref "R3") (pin "2") (pinfunction "2_2") (pintype "passive"))
      (node (ref "R4") (pin "1") (pinfunction "1_1") (pintype "passive"))
      (node (ref "R42") (pin "2") (pinfunction "2_2") (pintype "passive"))
      (node (ref "R43") (pin "2") (pinfunction "2_2") (pintype "passive"))
      (node (ref "R60") (pin "2") (pinfunction "2_2") (pintype "passive"))
      (node (ref "R61") (pin "2") (pinfunction "2_2") (pintype "passive"))
      (node (ref "R83") (pin "2") (pinfunction "2_2") (pintype "passive"))
      (node (ref "R84") (pin "2") (pinfunction "2_2") (pintype "passive"))
      (node (ref "R85") (pin "2") (pinfunction "2_2") (pintype "passive"))
      (node (ref "R86") (pin "2") (pinfunction "2_2") (pintype "passive"))
      (node (ref "U1") (pin "P$24") (pinfunction "VCC_P$24") (pintype "power_in"))
      (node (ref "U18") (pin "P$6") (pinfunction "VS_P$6") (pintype "bidirectional"))
      (node (ref "U19") (pin "P$6") (pinfunction "VS_P$6") (pintype "bidirectional"))
      (node (ref "U2") (pin "P$8") (pinfunction "VDD_P$8") (pintype "bidirectional"))
      (node (ref "U8") (pin "P$6") (pinfunction "VS_P$6") (pintype "bidirectional"))
      (node (ref "U9") (pin "P$6") (pinfunction "VS_P$6") (pintype "bidirectional"))
      (node (ref "V12") (pin "P$1") (pinfunction "P$1_P$1") (pintype "bidirectional"))
    )
    (net (code "2") (name "5V") (class "Default")
      (node (ref "T1") (pin "+") (pinfunction "+_+") (pintype "bidirectional"))
      (node (ref "T2") (pin "+") (pinfunction "+_+") (pintype "bidirectional"))
      (node (ref "T3") (pin "+") (pinfunction "+_+") (pintype "bidirectional"))
      (node (ref "T4") (pin "+") (pinfunction "+_+") (pintype "bidirectional"))
      (node (ref "V7") (pin "P$1") (pinfunction "P$1_P$1") (pintype "bidirectional"))
    )
    (net (code "3") (name "GND") (class "Default")
      (node (ref "C1") (pin "2") (pinfunction "P$2_2") (pintype "passive"))
      (node (ref "C11") (pin "2") (pinfunction "P$2_2") (pintype "passive"))
      (node (ref "C12") (pin "2") (pinfunction "P$2_2") (pintype "passive"))
      (node (ref "C13") (pin "1") (pinfunction "P$1_1") (pintype "passive"))
      (node (ref "C14") (pin "1") (pinfunction "P$1_1") (pintype "passive"))
      (node (ref "C15") (pin "1") (pinfunction "P$1_1") (pintype "passive"))
      (node (ref "C16") (pin "1") (pinfunction "P$1_1") (pintype "passive"))
      (node (ref "C17") (pin "2") (pinfunction "P$2_2") (pintype "passive"))
      (node (ref "C18") (pin "2") (pinfunction "P$2_2") (pintype "passive"))
      (node (ref "C2") (pin "2") (pinfunction "P$2_2") (pintype "passive"))
      (node (ref "C21") (pin "2") (pinfunction "P$2_2") (pintype "passive"))
      (node (ref "C22") (pin "2") (pinfunction "P$2_2") (pintype "passive"))
      (node (ref "C23") (pin "2") (pinfunction "P$2_2") (pintype "passive"))
      (node (ref "C24") (pin "2") (pinfunction "P$2_2") (pintype "passive"))
      (node (ref "C25") (pin "1") (pinfunction "P$1_1") (pintype "passive"))
      (node (ref "C26") (pin "1") (pinfunction "P$1_1") (pintype "passive"))
      (node (ref "C28") (pin "2") (pinfunction "P$2_2") (pintype "passive"))
      (node (ref "C29") (pin "1") (pinfunction "P$1_1") (pintype "passive"))
      (node (ref "C3") (pin "2") (pinfunction "P$2_2") (pintype "passive"))
      (node (ref "C30") (pin "2") (pinfunction "P$2_2") (pintype "passive"))
      (node (ref "C31") (pin "2") (pinfunction "P$2_2") (pintype "passive"))
      (node (ref "C32") (pin "1") (pinfunction "P$1_1") (pintype "passive"))
      (node (ref "C33") (pin "1") (pinfunction "P$1_1") (pintype "passive"))
      (node (ref "C35") (pin "2") (pinfunction "P$2_2") (pintype "passive"))
      (node (ref "C36") (pin "1") (pinfunction "P$1_1") (pintype "passive"))
      (node (ref "C37") (pin "2") (pinfunction "P$2_2") (pintype "passive"))
      (node (ref "C38") (pin "2") (pinfunction "P$2_2") (pintype "passive"))
      (node (ref "C4") (pin "2") (pinfunction "P$2_2") (pintype "passive"))
      (node (ref "C5") (pin "2") (pinfunction "P$2_2") (pintype "passive"))
      (node (ref "C6") (pin "2") (pinfunction "P$2_2") (pintype "passive"))
      (node (ref "C7") (pin "2") (pinfunction "P$2_2") (pintype "passive"))
      (node (ref "C8") (pin "2") (pinfunction "P$2_2") (pintype "passive"))
      (node (ref "D4") (pin "A") (pinfunction "A_A") (pintype "passive"))
      (node (ref "D5") (pin "A") (pinfunction "A_A") (pintype "passive"))
      (node (ref "R11") (pin "1") (pinfunction "1_1") (pintype "passive"))
      (node (ref "R14") (pin "1") (pinfunction "1_1") (pintype "passive"))
      (node (ref "R19") (pin "1") (pinfunction "1_1") (pintype "passive"))
      (node (ref "R21") (pin "2") (pinfunction "2_2") (pintype "passive"))
      (node (ref "R23") (pin "1") (pinfunction "1_1") (pintype "passive"))
      (node (ref "R25") (pin "1") (pinfunction "1_1") (pintype "passive"))
      (node (ref "R26") (pin "2") (pinfunction "2_2") (pintype "passive"))
      (node (ref "R28") (pin "1") (pinfunction "1_1") (pintype "passive"))
      (node (ref "R30") (pin "2") (pinfunction "2_2") (pintype "passive"))
      (node (ref "R32") (pin "1") (pinfunction "1_1") (pintype "passive"))
      (node (ref "R34") (pin "1") (pinfunction "1_1") (pintype "passive"))
      (node (ref "R35") (pin "1") (pinfunction "1_1") (pintype "passive"))
      (node (ref "R36") (pin "1") (pinfunction "1_1") (pintype "passive"))
      (node (ref "R40") (pin "1") (pinfunction "1_1") (pintype "passive"))
      (node (ref "R41") (pin "P$1") (pinfunction "1_P$1") (pintype "passive"))
      (node (ref "R44") (pin "1") (pinfunction "1_1") (pintype "passive"))
      (node (ref "R46") (pin "1") (pinfunction "1_1") (pintype "passive"))
      (node (ref "R48") (pin "1") (pinfunction "1_1") (pintype "passive"))
      (node (ref "R50") (pin "1") (pinfunction "1_1") (pintype "passive"))
      (node (ref "R51") (pin "2") (pinfunction "2_2") (pintype "passive"))
      (node (ref "R58") (pin "1") (pinfunction "1_1") (pintype "passive"))
      (node (ref "R59") (pin "P$1") (pinfunction "1_P$1") (pintype "passive"))
      (node (ref "R6") (pin "2") (pinfunction "2_2") (pintype "passive"))
      (node (ref "R62") (pin "1") (pinfunction "1_1") (pintype "passive"))
      (node (ref "R64") (pin "1") (pinfunction "1_1") (pintype "passive"))
      (node (ref "R66") (pin "1") (pinfunction "1_1") (pintype "passive"))
      (node (ref "R68") (pin "1") (pinfunction "1_1") (pintype "passive"))
      (node (ref "R69") (pin "2") (pinfunction "2_2") (pintype "passive"))
      (node (ref "R76") (pin "1") (pinfunction "1_1") (pintype "passive"))
      (node (ref "R77") (pin "1") (pinfunction "1_1") (pintype "passive"))
      (node (ref "R8") (pin "1") (pinfunction "1_1") (pintype "passive"))
      (node (ref "R80") (pin "1") (pinfunction "1_1") (pintype "passive"))
      (node (ref "R9") (pin "1") (pinfunction "1_1") (pintype "passive"))
      (node (ref "SW1") (pin "P$1") (pinfunction "GND_P$1") (pintype "bidirectional"))
      (node (ref "SW2") (pin "P$1") (pinfunction "GND_P$1") (pintype "bidirectional"))
      (node (ref "U1") (pin "P$12") (pinfunction "GND_P$12") (pintype "power_in"))
      (node (ref "U1") (pin "P$2") (pinfunction "A1_P$2") (pintype "bidirectional"))
      (node (ref "U1") (pin "P$21") (pinfunction "A0_P$21") (pintype "bidirectional"))
      (node (ref "U1") (pin "P$3") (pinfunction "A2_P$3") (pintype "bidirectional"))
      (node (ref "U10") (pin "P$4") (pinfunction "GND_P$4") (pintype "bidirectional"))
      (node (ref "U10") (pin "P$6") (pinfunction "NC_P$6") (pintype "bidirectional"))
      (node (ref "U10") (pin "P$7") (pinfunction "NC_P$7") (pintype "bidirectional"))
      (node (ref "U11") (pin "P$4") (pinfunction "GND_P$4") (pintype "bidirectional"))
      (node (ref "U11") (pin "P$6") (pinfunction "NC_P$6") (pintype "bidirectional"))
      (node (ref "U11") (pin "P$7") (pinfunction "NC_P$7") (pintype "bidirectional"))
      (node (ref "U12") (pin "P$2") (pinfunction "GND_P$2") (pintype "bidirectional"))
      (node (ref "U13") (pin "P$2") (pinfunction "GND_P$2") (pintype "bidirectional"))
      (node (ref "U14") (pin "P$12") (pinfunction "NTC_P$12") (pintype "bidirectional"))
      (node (ref "U14") (pin "P$17") (pinfunction "GND_P$17") (pintype "bidirectional"))
      (node (ref "U14") (pin "P$5") (pinfunction "GND_P$5") (pintype "bidirectional"))
      (node (ref "U14") (pin "P$7") (pinfunction "FREQ_P$7") (pintype "bidirectional"))
      (node (ref "U16") (pin "P$12") (pinfunction "NTC_P$12") (pintype "bidirectional"))
      (node (ref "U16") (pin "P$17") (pinfunction "GND_P$17") (pintype "bidirectional"))
      (node (ref "U16") (pin "P$5") (pinfunction "GND_P$5") (pintype "bidirectional"))
      (node (ref "U16") (pin "P$7") (pinfunction "FREQ_P$7") (pintype "bidirectional"))
      (node (ref "U18") (pin "P$1") (pinfunction "-IN_P$1") (pintype "bidirectional"))
      (node (ref "U18") (pin "P$2") (pinfunction "GND_P$2") (pintype "bidirectional"))
      (node (ref "U18") (pin "P$4") (pinfunction "NC_P$4") (pintype "bidirectional"))
      (node (ref "U19") (pin "P$1") (pinfunction "-IN_P$1") (pintype "bidirectional"))
      (node (ref "U19") (pin "P$2") (pinfunction "GND_P$2") (pintype "bidirectional"))
      (node (ref "U19") (pin "P$4") (pinfunction "NC_P$4") (pintype "bidirectional"))
      (node (ref "U2") (pin "P$7") (pinfunction "GND_P$7") (pintype "bidirectional"))
      (node (ref "U3") (pin "P$2") (pinfunction "GND_P$2") (pintype "bidirectional"))
      (node (ref "U3") (pin "P$3") (pinfunction "CNTL_P$3") (pintype "bidirectional"))
      (node (ref "U4") (pin "P$11") (pinfunction "NC_P$11") (pintype "bidirectional"))
      (node (ref "U4") (pin "P$12") (pinfunction "NTC_P$12") (pintype "bidirectional"))
      (node (ref "U4") (pin "P$17") (pinfunction "GND_P$17") (pintype "bidirectional"))
      (node (ref "U4") (pin "P$5") (pinfunction "GND_P$5") (pintype "bidirectional"))
      (node (ref "U4") (pin "P$7") (pinfunction "FREQ_P$7") (pintype "bidirectional"))
      (node (ref "U5") (pin "P$11") (pinfunction "NC_P$11") (pintype "bidirectional"))
      (node (ref "U5") (pin "P$12") (pinfunction "NTC_P$12") (pintype "bidirectional"))
      (node (ref "U5") (pin "P$17") (pinfunction "GND_P$17") (pintype "bidirectional"))
      (node (ref "U5") (pin "P$5") (pinfunction "GND_P$5") (pintype "bidirectional"))
      (node (ref "U5") (pin "P$7") (pinfunction "FREQ_P$7") (pintype "bidirectional"))
      (node (ref "U6") (pin "P$1") (pinfunction "S2_P$1") (pintype "bidirectional"))
      (node (ref "U6") (pin "P$3") (pinfunction "TST_P$3") (pintype "bidirectional"))
      (node (ref "U6") (pin "P$4") (pinfunction "VSS_P$4") (pintype "bidirectional"))
      (node (ref "U7") (pin "P$1") (pinfunction "S2_P$1") (pintype "bidirectional"))
      (node (ref "U7") (pin "P$3") (pinfunction "TST_P$3") (pintype "bidirectional"))
      (node (ref "U7") (pin "P$4") (pinfunction "VSS_P$4") (pintype "bidirectional"))
      (node (ref "U8") (pin "P$2") (pinfunction "GND_P$2") (pintype "bidirectional"))
      (node (ref "U8") (pin "P$4") (pinfunction "NC_P$4") (pintype "bidirectional"))
      (node (ref "U9") (pin "P$2") (pinfunction "GND_P$2") (pintype "bidirectional"))
      (node (ref "U9") (pin "P$4") (pinfunction "NC_P$4") (pintype "bidirectional"))
      (node (ref "V1") (pin "P$1") (pinfunction "P$1_P$1") (pintype "bidirectional"))
      (node (ref "V2") (pin "P$1") (pinfunction "P$1_P$1") (pintype "bidirectional"))
      (node (ref "V28") (pin "P$1") (pinfunction "P$1_P$1") (pintype "bidirectional"))
      (node (ref "V3") (pin "P$1") (pinfunction "P$1_P$1") (pintype "bidirectional"))
      (node (ref "V36") (pin "P$1") (pinfunction "P$1_P$1") (pintype "bidirectional"))
      (node (ref "V4") (pin "P$1") (pinfunction "P$1_P$1") (pintype "bidirectional"))
    )
    (net (code "4") (name "L1_CHG") (class "Default")
      (node (ref "R15") (pin "2") (pinfunction "2_2") (pintype "passive"))
      (node (ref "R35") (pin "2") (pinfunction "2_2") (pintype "passive"))
      (node (ref "U4") (pin "P$16") (pinfunction "RUN_P$16") (pintype "bidirectional"))
      (node (ref "V20") (pin "P$1") (pinfunction "P$1_P$1") (pintype "bidirectional"))
      (node (ref "V48") (pin "P$1") (pinfunction "P$1_P$1") (pintype "bidirectional"))
    )
    (net (code "5") (name "L1_CHGN") (class "Default")
      (node (ref "R17") (pin "1") (pinfunction "1_1") (pintype "passive"))
      (node (ref "U1") (pin "P$8") (pinfunction "P04_P$8") (pintype "bidirectional"))
      (node (ref "U4") (pin "P$14") (pinfunction "~{CHRG}_P$14") (pintype "bidirectional"))
      (node (ref "V27") (pin "P$1") (pinfunction "P$1_P$1") (pintype "bidirectional"))
    )
    (net (code "6") (name "L1_DISG") (class "Default")
      (node (ref "U12") (pin "P$3") (pinfunction "CNTRL_P$3") (pintype "bidirectional"))
      (node (ref "V29") (pin "P$1") (pinfunction "P$1_P$1") (pintype "bidirectional"))
    )
    (net (code "7") (name "L1_FAULTN") (class "Default")
      (node (ref "R18") (pin "1") (pinfunction "1_1") (pintype "passive"))
      (node (ref "U1") (pin "P$9") (pinfunction "P05_P$9") (pintype "bidirectional"))
      (node (ref "U4") (pin "P$15") (pinfunction "~{FAULT}_P$15") (pintype "bidirectional"))
      (node (ref "V26") (pin "P$1") (pinfunction "P$1_P$1") (pintype "bidirectional"))
    )
    (net (code "8") (name "L1_PROG") (class "Default")
      (node (ref "R25") (pin "2") (pinfunction "2_2") (pintype "passive"))
      (node (ref "U4") (pin "P$13") (pinfunction "PROG_P$13") (pintype "bidirectional"))
    )
    (net (code "9") (name "L1_REF") (class "Default")
      (node (ref "R33") (pin "1") (pinfunction "1_1") (pintype "passive"))
      (node (ref "R34") (pin "2") (pinfunction "2_2") (pintype "passive"))
      (node (ref "V21") (pin "P$1") (pinfunction "P$1_P$1") (pintype "bidirectional"))
    )
    (net (code "10") (name "L1_SNS") (class "Default")
      (node (ref "U2") (pin "P$4") (pinfunction "VIN1_P$4") (pintype "bidirectional"))
      (node (ref "U8") (pin "P$5") (pinfunction "OUT_P$5") (pintype "bidirectional"))
    )
    (net (code "11") (name "L1_SNS+") (class "Default")
      (node (ref "LI-ION1") (pin "MINUS") (pinfunction "MINUS_MINUS") (pintype "power_in"))
      (node (ref "R31") (pin "P$2") (pinfunction "2_P$2") (pintype "passive"))
      (node (ref "U8") (pin "P$8") (pinfunction "+IN_P$8") (pintype "bidirectional"))
    )
    (net (code "12") (name "L1_SNS-") (class "Default")
      (node (ref "R31") (pin "P$1") (pinfunction "1_P$1") (pintype "passive"))
      (node (ref "U8") (pin "P$1") (pinfunction "-IN_P$1") (pintype "bidirectional"))
      (node (ref "V22") (pin "P$1") (pinfunction "P$1_P$1") (pintype "bidirectional"))
    )
    (net (code "13") (name "L1_ST") (class "Default")
      (node (ref "R37") (pin "1") (pinfunction "1_1") (pintype "passive"))
      (node (ref "U1") (pin "P$5") (pinfunction "P01_P$5") (pintype "bidirectional"))
      (node (ref "U12") (pin "P$4") (pinfunction "STAT_P$4") (pintype "bidirectional"))
    )
    (net (code "14") (name "L1_TEMP") (class "Default")
      (node (ref "T1") (pin "-") (pinfunction "-_-") (pintype "bidirectional"))
      (node (ref "V8") (pin "P$1") (pinfunction "P$1_P$1") (pintype "bidirectional"))
    )
    (net (code "15") (name "L2_CHG") (class "Default")
      (node (ref "R1") (pin "2") (pinfunction "2_2") (pintype "passive"))
      (node (ref "R36") (pin "2") (pinfunction "2_2") (pintype "passive"))
      (node (ref "U5") (pin "P$16") (pinfunction "RUN_P$16") (pintype "bidirectional"))
      (node (ref "V33") (pin "P$1") (pinfunction "P$1_P$1") (pintype "bidirectional"))
    )
    (net (code "16") (name "L2_CHGN") (class "Default")
      (node (ref "R2") (pin "1") (pinfunction "1_1") (pintype "passive"))
      (node (ref "U1") (pin "P$10") (pinfunction "P06_P$10") (pintype "bidirectional"))
      (node (ref "U5") (pin "P$14") (pinfunction "~{CHRG}_P$14") (pintype "bidirectional"))
    )
    (net (code "17") (name "L2_DISG") (class "Default")
      (node (ref "U13") (pin "P$3") (pinfunction "CNTRL_P$3") (pintype "bidirectional"))
      (node (ref "V30") (pin "P$1") (pinfunction "P$1_P$1") (pintype "bidirectional"))
    )
    (net (code "18") (name "L2_FAULTN") (class "Default")
      (node (ref "R3") (pin "1") (pinfunction "1_1") (pintype "passive"))
      (node (ref "U1") (pin "P$11") (pinfunction "P07_P$11") (pintype "bidirectional"))
      (node (ref "U5") (pin "P$15") (pinfunction "~{FAULT}_P$15") (pintype "bidirectional"))
    )
    (net (code "19") (name "L2_PROG") (class "Default")
      (node (ref "R9") (pin "2") (pinfunction "2_2") (pintype "passive"))
      (node (ref "U5") (pin "P$13") (pinfunction "PROG_P$13") (pintype "bidirectional"))
    )
    (net (code "20") (name "L2_REF") (class "Default")
      (node (ref "R16") (pin "1") (pinfunction "1_1") (pintype "passive"))
      (node (ref "R19") (pin "2") (pinfunction "2_2") (pintype "passive"))
      (node (ref "V31") (pin "P$1") (pinfunction "P$1_P$1") (pintype "bidirectional"))
    )
    (net (code "21") (name "L2_SNS") (class "Default")
      (node (ref "U2") (pin "P$3") (pinfunction "VIN0_P$3") (pintype "bidirectional"))
      (node (ref "U9") (pin "P$5") (pinfunction "OUT_P$5") (pintype "bidirectional"))
    )
    (net (code "22") (name "L2_SNS+") (class "Default")
      (node (ref "LI-ION2") (pin "MINUS") (pinfunction "MINUS_MINUS") (pintype "power_in"))
      (node (ref "R12") (pin "P$2") (pinfunction "2_P$2") (pintype "passive"))
      (node (ref "U9") (pin "P$8") (pinfunction "+IN_P$8") (pintype "bidirectional"))
    )
    (net (code "23") (name "L2_SNS-") (class "Default")
      (node (ref "R12") (pin "P$1") (pinfunction "1_P$1") (pintype "passive"))
      (node (ref "U9") (pin "P$1") (pinfunction "-IN_P$1") (pintype "bidirectional"))
      (node (ref "V24") (pin "P$1") (pinfunction "P$1_P$1") (pintype "bidirectional"))
    )
    (net (code "24") (name "L2_ST") (class "Default")
      (node (ref "R38") (pin "1") (pinfunction "1_1") (pintype "passive"))
      (node (ref "U1") (pin "P$4") (pinfunction "P00_P$4") (pintype "bidirectional"))
      (node (ref "U13") (pin "P$4") (pinfunction "STAT_P$4") (pintype "bidirectional"))
    )
    (net (code "25") (name "L2_TEMP") (class "Default")
      (node (ref "T2") (pin "-") (pinfunction "-_-") (pintype "bidirectional"))
      (node (ref "V9") (pin "P$1") (pinfunction "P$1_P$1") (pintype "bidirectional"))
    )
    (net (code "26") (name "LF1_REF") (class "Default")
      (node (ref "R49") (pin "2") (pinfunction "2_2") (pintype "passive"))
      (node (ref "R50") (pin "2") (pinfunction "2_2") (pintype "passive"))
      (node (ref "V41") (pin "P$1") (pinfunction "P$1_P$1") (pintype "bidirectional"))
    )
    (net (code "27") (name "LF1_TEMP") (class "Default")
      (node (ref "T3") (pin "-") (pinfunction "-_-") (pintype "bidirectional"))
      (node (ref "V10") (pin "P$1") (pinfunction "P$1_P$1") (pintype "bidirectional"))
    )
    (net (code "28") (name "LF2_REF") (class "Default")
      (node (ref "R47") (pin "1") (pinfunction "1_1") (pintype "passive"))
      (node (ref "R48") (pin "2") (pinfunction "2_2") (pintype "passive"))
      (node (ref "V42") (pin "P$1") (pinfunction "P$1_P$1") (pintype "bidirectional"))
    )
    (net (code "29") (name "LF3_REF") (class "Default")
      (node (ref "R67") (pin "2") (pinfunction "2_2") (pintype "passive"))
      (node (ref "R68") (pin "2") (pinfunction "2_2") (pintype "passive"))
      (node (ref "V49") (pin "P$1") (pinfunction "P$1_P$1") (pintype "bidirectional"))
    )
    (net (code "30") (name "LF3_TEMP") (class "Default")
      (node (ref "T4") (pin "-") (pinfunction "-_-") (pintype "bidirectional"))
      (node (ref "V11") (pin "P$1") (pinfunction "P$1_P$1") (pintype "bidirectional"))
    )
    (net (code "31") (name "LF4_REF") (class "Default")
      (node (ref "R65") (pin "1") (pinfunction "1_1") (pintype "passive"))
      (node (ref "R66") (pin "2") (pinfunction "2_2") (pintype "passive"))
      (node (ref "V50") (pin "P$1") (pinfunction "P$1_P$1") (pintype "bidirectional"))
    )
    (net (code "32") (name "LFB1_SNS+") (class "Default")
      (node (ref "LIFEPO42") (pin "MINUS") (pinfunction "MINUS_MINUS") (pintype "power_in"))
      (node (ref "R41") (pin "P$2") (pinfunction "2_P$2") (pintype "passive"))
      (node (ref "U18") (pin "P$8") (pinfunction "+IN_P$8") (pintype "bidirectional"))
    )
    (net (code "33") (name "LFB2_SNS+") (class "Default")
      (node (ref "LIFEPO44") (pin "MINUS") (pinfunction "MINUS_MINUS") (pintype "power_in"))
      (node (ref "R59") (pin "P$2") (pinfunction "2_P$2") (pintype "passive"))
      (node (ref "U19") (pin "P$8") (pinfunction "+IN_P$8") (pintype "bidirectional"))
    )
    (net (code "34") (name "LF_B1") (class "Default")
      (node (ref "C30") (pin "1") (pinfunction "P$1_1") (pintype "passive"))
      (node (ref "SW1") (pin "P$5") (pinfunction "OUT_P$5") (pintype "power_in"))
      (node (ref "SW1") (pin "P$6") (pinfunction "OUT_P$6") (pintype "power_in"))
      (node (ref "SW1") (pin "P$7") (pinfunction "OUT_P$7") (pintype "power_in"))
      (node (ref "V45") (pin "P$1") (pinfunction "P$1_P$1") (pintype "bidirectional"))
    )
    (net (code "35") (name "LF_B1_BT") (class "Default")
      (node (ref "U1") (pin "P$16") (pinfunction "P13_P$16") (pintype "bidirectional"))
    )
    (net (code "36") (name "LF_B1_CHG") (class "Default")
      (node (ref "R44") (pin "2") (pinfunction "2_2") (pintype "passive"))
      (node (ref "U14") (pin "P$16") (pinfunction "RUN_P$16") (pintype "bidirectional"))
      (node (ref "V32") (pin "P$1") (pinfunction "P$1_P$1") (pintype "bidirectional"))
      (node (ref "V35") (pin "P$1") (pinfunction "P$1_P$1") (pintype "bidirectional"))
    )
    (net (code "37") (name "LF_B1_CHGN") (class "Default")
      (node (ref "R42") (pin "1") (pinfunction "1_1") (pintype "passive"))
      (node (ref "U1") (pin "P$20") (pinfunction "P17_P$20") (pintype "bidirectional"))
      (node (ref "U14") (pin "P$14") (pinfunction "~{CHRG}_P$14") (pintype "bidirectional"))
    )
    (net (code "38") (name "LF_B1_FAULTN") (class "Default")
      (node (ref "R43") (pin "1") (pinfunction "1_1") (pintype "passive"))
      (node (ref "U1") (pin "P$19") (pinfunction "P16_P$19") (pintype "bidirectional"))
      (node (ref "U14") (pin "P$15") (pinfunction "~{FAULT}_P$15") (pintype "bidirectional"))
    )
    (net (code "39") (name "LF_B1_OSNS") (class "Default")
      (node (ref "C31") (pin "1") (pinfunction "P$1_1") (pintype "passive"))
      (node (ref "R79") (pin "1") (pinfunction "1_1") (pintype "passive"))
      (node (ref "V46") (pin "P$1") (pinfunction "P$1_P$1") (pintype "bidirectional"))
    )
    (net (code "40") (name "LF_B1_OUTEN") (class "Default")
      (node (ref "R78") (pin "1") (pinfunction "1_1") (pintype "passive"))
      (node (ref "V43") (pin "P$1") (pinfunction "P$1_P$1") (pintype "bidirectional"))
    )
    (net (code "41") (name "LF_B1_SNS") (class "Default")
      (node (ref "U18") (pin "P$5") (pinfunction "OUT_P$5") (pintype "bidirectional"))
      (node (ref "V40") (pin "P$1") (pinfunction "P$1_P$1") (pintype "bidirectional"))
    )
    (net (code "42") (name "LF_B1_TT") (class "Default")
      (node (ref "U1") (pin "P$15") (pinfunction "P12_P$15") (pintype "bidirectional"))
    )
    (net (code "43") (name "LF_B2") (class "Default")
      (node (ref "C37") (pin "1") (pinfunction "P$1_1") (pintype "passive"))
      (node (ref "SW2") (pin "P$5") (pinfunction "OUT_P$5") (pintype "power_in"))
      (node (ref "SW2") (pin "P$6") (pinfunction "OUT_P$6") (pintype "power_in"))
      (node (ref "SW2") (pin "P$7") (pinfunction "OUT_P$7") (pintype "power_in"))
      (node (ref "V53") (pin "P$1") (pinfunction "P$1_P$1") (pintype "bidirectional"))
    )
    (net (code "44") (name "LF_B2_BT") (class "Default")
      (node (ref "U1") (pin "P$13") (pinfunction "P10_P$13") (pintype "bidirectional"))
    )
    (net (code "45") (name "LF_B2_CHG") (class "Default")
      (node (ref "R62") (pin "2") (pinfunction "2_2") (pintype "passive"))
      (node (ref "U16") (pin "P$16") (pinfunction "RUN_P$16") (pintype "bidirectional"))
      (node (ref "V47") (pin "P$1") (pinfunction "P$1_P$1") (pintype "bidirectional"))
    )
    (net (code "46") (name "LF_B2_CHGN") (class "Default")
      (node (ref "R60") (pin "1") (pinfunction "1_1") (pintype "passive"))
      (node (ref "U1") (pin "P$17") (pinfunction "P14_P$17") (pintype "bidirectional"))
      (node (ref "U16") (pin "P$14") (pinfunction "~{CHRG}_P$14") (pintype "bidirectional"))
    )
    (net (code "47") (name "LF_B2_FAULTN") (class "Default")
      (node (ref "R61") (pin "1") (pinfunction "1_1") (pintype "passive"))
      (node (ref "U1") (pin "P$18") (pinfunction "P15_P$18") (pintype "bidirectional"))
      (node (ref "U16") (pin "P$15") (pinfunction "~{FAULT}_P$15") (pintype "bidirectional"))
    )
    (net (code "48") (name "LF_B2_OSNS") (class "Default")
      (node (ref "C38") (pin "1") (pinfunction "P$1_1") (pintype "passive"))
      (node (ref "R82") (pin "1") (pinfunction "1_1") (pintype "passive"))
      (node (ref "V99") (pin "P$1") (pinfunction "P$1_P$1") (pintype "bidirectional"))
    )
    (net (code "49") (name "LF_B2_OUTEN") (class "Default")
      (node (ref "R81") (pin "1") (pinfunction "1_1") (pintype "passive"))
      (node (ref "V51") (pin "P$1") (pinfunction "P$1_P$1") (pintype "bidirectional"))
    )
    (net (code "50") (name "LF_B2_SNS") (class "Default")
      (node (ref "U19") (pin "P$5") (pinfunction "OUT_P$5") (pintype "bidirectional"))
      (node (ref "V44") (pin "P$1") (pinfunction "P$1_P$1") (pintype "bidirectional"))
    )
    (net (code "51") (name "LF_B2_TT") (class "Default")
      (node (ref "U1") (pin "P$14") (pinfunction "P11_P$14") (pintype "bidirectional"))
    )
    (net (code "52") (name "LIFE1") (class "Default")
      (node (ref "C28") (pin "1") (pinfunction "P$1_1") (pintype "passive"))
      (node (ref "D4") (pin "C") (pinfunction "C_C") (pintype "passive"))
      (node (ref "F3") (pin "P$1") (pinfunction "P$1_P$1") (pintype "passive"))
      (node (ref "F4") (pin "P$1") (pinfunction "P$1_P$1") (pintype "passive"))
      (node (ref "LIFEPO41") (pin "PLUS") (pinfunction "PLUS_PLUS") (pintype "power_in"))
      (node (ref "R49") (pin "1") (pinfunction "1_1") (pintype "passive"))
      (node (ref "R53") (pin "2") (pinfunction "2_2") (pintype "passive"))
      (node (ref "U14") (pin "P$9") (pinfunction "BAT_P$9") (pintype "bidirectional"))
    )
    (net (code "53") (name "LIFE1FUSEOUT") (class "Default")
      (node (ref "F3") (pin "P$2") (pinfunction "P$2_P$2") (pintype "passive"))
      (node (ref "F4") (pin "P$2") (pinfunction "P$2_P$2") (pintype "passive"))
      (node (ref "SW1") (pin "PAD") (pinfunction "VB_PAD") (pintype "power_in"))
    )
    (net (code "54") (name "LIFE3") (class "Default")
      (node (ref "C35") (pin "1") (pinfunction "P$1_1") (pintype "passive"))
      (node (ref "D5") (pin "C") (pinfunction "C_C") (pintype "passive"))
      (node (ref "F5") (pin "P$1") (pinfunction "P$1_P$1") (pintype "passive"))
      (node (ref "F6") (pin "P$1") (pinfunction "P$1_P$1") (pintype "passive"))
      (node (ref "LIFEPO43") (pin "PLUS") (pinfunction "PLUS_PLUS") (pintype "power_in"))
      (node (ref "R67") (pin "1") (pinfunction "1_1") (pintype "passive"))
      (node (ref "R71") (pin "2") (pinfunction "2_2") (pintype "passive"))
      (node (ref "U16") (pin "P$9") (pinfunction "BAT_P$9") (pintype "bidirectional"))
    )
    (net (code "55") (name "LIFE3FUSEOUT") (class "Default")
      (node (ref "F5") (pin "P$2") (pinfunction "P$2_P$2") (pintype "passive"))
      (node (ref "F6") (pin "P$2") (pinfunction "P$2_P$2") (pintype "passive"))
      (node (ref "SW2") (pin "PAD") (pinfunction "VB_PAD") (pintype "power_in"))
    )
    (net (code "56") (name "LION1") (class "Default")
      (node (ref "C11") (pin "1") (pinfunction "P$1_1") (pintype "passive"))
      (node (ref "F1") (pin "1") (pinfunction "P$1_1") (pintype "passive"))
      (node (ref "LI-ION1") (pin "PLUS") (pinfunction "PLUS_PLUS") (pintype "power_in"))
      (node (ref "R33") (pin "2") (pinfunction "2_2") (pintype "passive"))
      (node (ref "R7") (pin "2") (pinfunction "2_2") (pintype "passive"))
      (node (ref "U4") (pin "P$10") (pinfunction "BATSNS_P$10") (pintype "bidirectional"))
      (node (ref "U4") (pin "P$9") (pinfunction "BAT_P$9") (pintype "bidirectional"))
    )
    (net (code "57") (name "LION1_OUT") (class "Default")
      (node (ref "C15") (pin "2") (pinfunction "P$2_2") (pintype "passive"))
      (node (ref "F1") (pin "2") (pinfunction "P$2_2") (pintype "passive"))
      (node (ref "U12") (pin "P$1") (pinfunction "IN_P$1") (pintype "bidirectional"))
    )
    (net (code "58") (name "LION2") (class "Default")
      (node (ref "C12") (pin "1") (pinfunction "P$1_1") (pintype "passive"))
      (node (ref "F2") (pin "1") (pinfunction "P$1_1") (pintype "passive"))
      (node (ref "LI-ION2") (pin "PLUS") (pinfunction "PLUS_PLUS") (pintype "power_in"))
      (node (ref "R16") (pin "2") (pinfunction "2_2") (pintype "passive"))
      (node (ref "R22") (pin "2") (pinfunction "2_2") (pintype "passive"))
      (node (ref "U5") (pin "P$10") (pinfunction "BATSNS_P$10") (pintype "bidirectional"))
      (node (ref "U5") (pin "P$9") (pinfunction "BAT_P$9") (pintype "bidirectional"))
    )
    (net (code "59") (name "LION2_OUT") (class "Default")
      (node (ref "C16") (pin "2") (pinfunction "P$2_2") (pintype "passive"))
      (node (ref "F2") (pin "2") (pinfunction "P$2_2") (pintype "passive"))
      (node (ref "U13") (pin "P$1") (pinfunction "IN_P$1") (pintype "bidirectional"))
    )
    (net (code "60") (name "L_OUT") (class "Default")
      (node (ref "C21") (pin "1") (pinfunction "P$1_1") (pintype "passive"))
      (node (ref "C22") (pin "1") (pinfunction "P$1_1") (pintype "passive"))
      (node (ref "D2") (pin "C") (pinfunction "C_C") (pintype "bidirectional"))
      (node (ref "D3") (pin "C") (pinfunction "C_C") (pintype "bidirectional"))
      (node (ref "R37") (pin "2") (pinfunction "2_2") (pintype "passive"))
      (node (ref "R38") (pin "2") (pinfunction "2_2") (pintype "passive"))
      (node (ref "R39") (pin "2") (pinfunction "2_2") (pintype "passive"))
      (node (ref "U12") (pin "P$5") (pinfunction "OUT_P$5") (pintype "bidirectional"))
      (node (ref "U13") (pin "P$5") (pinfunction "OUT_P$5") (pintype "bidirectional"))
      (node (ref "V34") (pin "P$1") (pinfunction "P$1_P$1") (pintype "bidirectional"))
    )
    (net (code "61") (name "L_REF") (class "Default")
      (node (ref "R39") (pin "1") (pinfunction "1_1") (pintype "passive"))
      (node (ref "R40") (pin "2") (pinfunction "2_2") (pintype "passive"))
      (node (ref "U2") (pin "P$5") (pinfunction "VIN2_P$5") (pintype "bidirectional"))
    )
    (net (code "62") (name "Net-(C7-P$1)") (class "Default")
      (node (ref "C7") (pin "1") (pinfunction "P$1_1") (pintype "passive"))
      (node (ref "U4") (pin "P$1") (pinfunction "INTVCC_P$1") (pintype "bidirectional"))
    )
    (net (code "63") (name "Net-(C8-P$1)") (class "Default")
      (node (ref "C8") (pin "1") (pinfunction "P$1_1") (pintype "passive"))
      (node (ref "U5") (pin "P$1") (pinfunction "INTVCC_P$1") (pintype "bidirectional"))
    )
    (net (code "64") (name "Net-(C9-P$1)") (class "Default")
      (node (ref "C9") (pin "1") (pinfunction "P$1_1") (pintype "passive"))
      (node (ref "U4") (pin "P$2") (pinfunction "BOOST_P$2") (pintype "bidirectional"))
    )
    (net (code "65") (name "Net-(C9-P$2)") (class "Default")
      (node (ref "C9") (pin "2") (pinfunction "P$2_2") (pintype "passive"))
      (node (ref "L1") (pin "P$1") (pinfunction "P$1_P$1") (pintype "passive"))
      (node (ref "U4") (pin "P$4") (pinfunction "SW_P$4") (pintype "bidirectional"))
    )
    (net (code "66") (name "Net-(C10-P$1)") (class "Default")
      (node (ref "C10") (pin "1") (pinfunction "P$1_1") (pintype "passive"))
      (node (ref "U5") (pin "P$2") (pinfunction "BOOST_P$2") (pintype "bidirectional"))
    )
    (net (code "67") (name "Net-(C10-P$2)") (class "Default")
      (node (ref "C10") (pin "2") (pinfunction "P$2_2") (pintype "passive"))
      (node (ref "L2") (pin "P$1") (pinfunction "P$1_P$1") (pintype "passive"))
      (node (ref "U5") (pin "P$4") (pinfunction "SW_P$4") (pintype "bidirectional"))
    )
    (net (code "68") (name "Net-(C13-P$2)") (class "Default")
      (node (ref "C13") (pin "2") (pinfunction "P$2_2") (pintype "passive"))
      (node (ref "R7") (pin "1") (pinfunction "1_1") (pintype "passive"))
      (node (ref "U6") (pin "P$5") (pinfunction "VCC_P$5") (pintype "bidirectional"))
    )
    (net (code "69") (name "Net-(C14-P$2)") (class "Default")
      (node (ref "C14") (pin "2") (pinfunction "P$2_2") (pintype "passive"))
      (node (ref "R22") (pin "1") (pinfunction "1_1") (pintype "passive"))
      (node (ref "U7") (pin "P$5") (pinfunction "VCC_P$5") (pintype "bidirectional"))
    )
    (net (code "70") (name "Net-(C19-P$1)") (class "Default")
      (node (ref "C19") (pin "1") (pinfunction "P$1_1") (pintype "passive"))
      (node (ref "C23") (pin "1") (pinfunction "P$1_1") (pintype "passive"))
      (node (ref "D2") (pin "A") (pinfunction "A_A") (pintype "bidirectional"))
      (node (ref "U10") (pin "P$1") (pinfunction "OUT_P$1") (pintype "bidirectional"))
      (node (ref "U10") (pin "P$2") (pinfunction "SENSE_P$2") (pintype "bidirectional"))
    )
    (net (code "71") (name "Net-(C19-P$2)") (class "Default")
      (node (ref "C19") (pin "2") (pinfunction "P$2_2") (pintype "passive"))
      (node (ref "U10") (pin "P$3") (pinfunction "BYP_P$3") (pintype "bidirectional"))
    )
    (net (code "72") (name "Net-(C20-P$1)") (class "Default")
      (node (ref "C20") (pin "1") (pinfunction "P$1_1") (pintype "passive"))
      (node (ref "C24") (pin "1") (pinfunction "P$1_1") (pintype "passive"))
      (node (ref "D3") (pin "A") (pinfunction "A_A") (pintype "bidirectional"))
      (node (ref "U11") (pin "P$1") (pinfunction "OUT_P$1") (pintype "bidirectional"))
      (node (ref "U11") (pin "P$2") (pinfunction "SENSE_P$2") (pintype "bidirectional"))
    )
    (net (code "73") (name "Net-(C20-P$2)") (class "Default")
      (node (ref "C20") (pin "2") (pinfunction "P$2_2") (pintype "passive"))
      (node (ref "U11") (pin "P$3") (pinfunction "BYP_P$3") (pintype "bidirectional"))
    )
    (net (code "74") (name "Net-(C26-P$2)") (class "Default")
      (node (ref "C26") (pin "2") (pinfunction "P$2_2") (pintype "passive"))
      (node (ref "U14") (pin "P$1") (pinfunction "INTVCC_P$1") (pintype "bidirectional"))
    )
    (net (code "75") (name "Net-(C27-P$1)") (class "Default")
      (node (ref "C27") (pin "1") (pinfunction "P$1_1") (pintype "passive"))
      (node (ref "L3") (pin "P$2") (pinfunction "P$2_P$2") (pintype "passive"))
      (node (ref "U14") (pin "P$4") (pinfunction "SW_P$4") (pintype "bidirectional"))
    )
    (net (code "76") (name "Net-(C27-P$2)") (class "Default")
      (node (ref "C27") (pin "2") (pinfunction "P$2_2") (pintype "passive"))
      (node (ref "U14") (pin "P$2") (pinfunction "BOOST_P$2") (pintype "bidirectional"))
    )
    (net (code "77") (name "Net-(C29-P$2)") (class "Default")
      (node (ref "C29") (pin "2") (pinfunction "P$2_2") (pintype "passive"))
      (node (ref "R77") (pin "2") (pinfunction "2_2") (pintype "passive"))
      (node (ref "R78") (pin "2") (pinfunction "2_2") (pintype "passive"))
      (node (ref "SW1") (pin "P$2") (pinfunction "CNTRL_P$2") (pintype "input"))
    )
    (net (code "78") (name "Net-(C33-P$2)") (class "Default")
      (node (ref "C33") (pin "2") (pinfunction "P$2_2") (pintype "passive"))
      (node (ref "U16") (pin "P$1") (pinfunction "INTVCC_P$1") (pintype "bidirectional"))
    )
    (net (code "79") (name "Net-(C34-P$1)") (class "Default")
      (node (ref "C34") (pin "1") (pinfunction "P$1_1") (pintype "passive"))
      (node (ref "L4") (pin "P$2") (pinfunction "P$2_P$2") (pintype "passive"))
      (node (ref "U16") (pin "P$4") (pinfunction "SW_P$4") (pintype "bidirectional"))
    )
    (net (code "80") (name "Net-(C34-P$2)") (class "Default")
      (node (ref "C34") (pin "2") (pinfunction "P$2_2") (pintype "passive"))
      (node (ref "U16") (pin "P$2") (pinfunction "BOOST_P$2") (pintype "bidirectional"))
    )
    (net (code "81") (name "Net-(C36-P$2)") (class "Default")
      (node (ref "C36") (pin "2") (pinfunction "P$2_2") (pintype "passive"))
      (node (ref "R80") (pin "2") (pinfunction "2_2") (pintype "passive"))
      (node (ref "R81") (pin "2") (pinfunction "2_2") (pintype "passive"))
      (node (ref "SW2") (pin "P$2") (pinfunction "CNTRL_P$2") (pintype "input"))
    )
    (net (code "82") (name "Net-(LIFEPO41-PadMINUS)") (class "Default")
      (node (ref "LIFEPO41") (pin "MINUS") (pinfunction "MINUS_MINUS") (pintype "power_in"))
      (node (ref "LIFEPO42") (pin "PLUS") (pinfunction "PLUS_PLUS") (pintype "power_in"))
      (node (ref "R47") (pin "2") (pinfunction "2_2") (pintype "passive"))
    )
    (net (code "83") (name "Net-(LIFEPO43-PadMINUS)") (class "Default")
      (node (ref "LIFEPO43") (pin "MINUS") (pinfunction "MINUS_MINUS") (pintype "power_in"))
      (node (ref "LIFEPO44") (pin "PLUS") (pinfunction "PLUS_PLUS") (pintype "power_in"))
      (node (ref "R65") (pin "2") (pinfunction "2_2") (pintype "passive"))
    )
    (net (code "84") (name "Net-(M1-G)") (class "Default")
      (node (ref "M1") (pin "P$4") (pinfunction "G_P$4") (pintype "bidirectional"))
      (node (ref "U3") (pin "P$5") (pinfunction "GATE_P$5") (pintype "bidirectional"))
    )
    (net (code "85") (name "Net-(SW1-ISNS)") (class "Default")
      (node (ref "R58") (pin "2") (pinfunction "2_2") (pintype "passive"))
      (node (ref "R79") (pin "2") (pinfunction "2_2") (pintype "passive"))
      (node (ref "SW1") (pin "P$3") (pinfunction "ISNS_P$3") (pintype "output"))
    )
    (net (code "86") (name "Net-(SW2-ISNS)") (class "Default")
      (node (ref "R76") (pin "2") (pinfunction "2_2") (pintype "passive"))
      (node (ref "R82") (pin "2") (pinfunction "2_2") (pintype "passive"))
      (node (ref "SW2") (pin "P$3") (pinfunction "ISNS_P$3") (pintype "output"))
    )
    (net (code "87") (name "Net-(U1-P03)") (class "Default")
      (node (ref "R32") (pin "2") (pinfunction "2_2") (pintype "passive"))
      (node (ref "U1") (pin "P$7") (pinfunction "P03_P$7") (pintype "bidirectional"))
    )
    (net (code "88") (name "Net-(U4-CHGSNS)") (class "Default")
      (node (ref "L1") (pin "P$2") (pinfunction "P$2_P$2") (pintype "passive"))
      (node (ref "U4") (pin "P$8") (pinfunction "CHGSNS_P$8") (pintype "bidirectional"))
    )
    (net (code "89") (name "Net-(U4-MPPT)") (class "Default")
      (node (ref "R27") (pin "1") (pinfunction "1_1") (pintype "passive"))
      (node (ref "R28") (pin "2") (pinfunction "2_2") (pintype "passive"))
      (node (ref "U4") (pin "P$6") (pinfunction "MPPT_P$6") (pintype "bidirectional"))
    )
    (net (code "90") (name "Net-(U5-CHGSNS)") (class "Default")
      (node (ref "L2") (pin "P$2") (pinfunction "P$2_P$2") (pintype "passive"))
      (node (ref "U5") (pin "P$8") (pinfunction "CHGSNS_P$8") (pintype "bidirectional"))
    )
    (net (code "91") (name "Net-(U5-MPPT)") (class "Default")
      (node (ref "R10") (pin "1") (pinfunction "1_1") (pintype "passive"))
      (node (ref "R11") (pin "2") (pinfunction "2_2") (pintype "passive"))
      (node (ref "U5") (pin "P$6") (pinfunction "MPPT_P$6") (pintype "bidirectional"))
    )
    (net (code "92") (name "Net-(U6-CS)") (class "Default")
      (node (ref "R8") (pin "2") (pinfunction "2_2") (pintype "passive"))
      (node (ref "U6") (pin "P$2") (pinfunction "CS_P$2") (pintype "bidirectional"))
    )
    (net (code "93") (name "Net-(U6-S1)") (class "Default")
      (node (ref "U6") (pin "P$6") (pinfunction "S1_P$6") (pintype "bidirectional"))
      (node (ref "V23") (pin "P$1") (pinfunction "P$1_P$1") (pintype "bidirectional"))
    )
    (net (code "94") (name "Net-(U7-CS)") (class "Default")
      (node (ref "R23") (pin "2") (pinfunction "2_2") (pintype "passive"))
      (node (ref "U7") (pin "P$2") (pinfunction "CS_P$2") (pintype "bidirectional"))
    )
    (net (code "95") (name "Net-(U7-S1)") (class "Default")
      (node (ref "U7") (pin "P$6") (pinfunction "S1_P$6") (pintype "bidirectional"))
      (node (ref "V25") (pin "P$1") (pinfunction "P$1_P$1") (pintype "bidirectional"))
    )
    (net (code "96") (name "Net-(U8-VREF1)") (class "Default")
      (node (ref "R4") (pin "2") (pinfunction "2_2") (pintype "passive"))
      (node (ref "R6") (pin "1") (pinfunction "1_1") (pintype "passive"))
      (node (ref "U8") (pin "P$3") (pinfunction "VREF2_P$3") (pintype "bidirectional"))
      (node (ref "U8") (pin "P$7") (pinfunction "VREF1_P$7") (pintype "bidirectional"))
    )
    (net (code "97") (name "Net-(U9-VREF1)") (class "Default")
      (node (ref "R20") (pin "2") (pinfunction "2_2") (pintype "passive"))
      (node (ref "R21") (pin "1") (pinfunction "1_1") (pintype "passive"))
      (node (ref "U9") (pin "P$3") (pinfunction "VREF2_P$3") (pintype "bidirectional"))
      (node (ref "U9") (pin "P$7") (pinfunction "VREF1_P$7") (pintype "bidirectional"))
    )
    (net (code "98") (name "Net-(U14-CHGSNS)") (class "Default")
      (node (ref "L3") (pin "P$1") (pinfunction "P$1_P$1") (pintype "passive"))
      (node (ref "U14") (pin "P$8") (pinfunction "CHGSNS_P$8") (pintype "bidirectional"))
    )
    (net (code "99") (name "Net-(U14-FB)") (class "Default")
      (node (ref "R52") (pin "2") (pinfunction "2_2") (pintype "passive"))
      (node (ref "R53") (pin "1") (pinfunction "1_1") (pintype "passive"))
      (node (ref "U14") (pin "P$10") (pinfunction "FB_P$10") (pintype "bidirectional"))
    )
    (net (code "100") (name "Net-(U14-FBG)") (class "Default")
      (node (ref "R52") (pin "1") (pinfunction "1_1") (pintype "passive"))
      (node (ref "U14") (pin "P$11") (pinfunction "FBG_P$11") (pintype "bidirectional"))
    )
    (net (code "101") (name "Net-(U14-MPPT)") (class "Default")
      (node (ref "R45") (pin "1") (pinfunction "1_1") (pintype "passive"))
      (node (ref "R46") (pin "2") (pinfunction "2_2") (pintype "passive"))
      (node (ref "U14") (pin "P$6") (pinfunction "MPPT_P$6") (pintype "bidirectional"))
    )
    (net (code "102") (name "Net-(U14-PROG)") (class "Default")
      (node (ref "R51") (pin "1") (pinfunction "1_1") (pintype "passive"))
      (node (ref "U14") (pin "P$13") (pinfunction "PROG_P$13") (pintype "bidirectional"))
    )
    (net (code "103") (name "Net-(U16-CHGSNS)") (class "Default")
      (node (ref "L4") (pin "P$1") (pinfunction "P$1_P$1") (pintype "passive"))
      (node (ref "U16") (pin "P$8") (pinfunction "CHGSNS_P$8") (pintype "bidirectional"))
    )
    (net (code "104") (name "Net-(U16-FB)") (class "Default")
      (node (ref "R70") (pin "2") (pinfunction "2_2") (pintype "passive"))
      (node (ref "R71") (pin "1") (pinfunction "1_1") (pintype "passive"))
      (node (ref "U16") (pin "P$10") (pinfunction "FB_P$10") (pintype "bidirectional"))
    )
    (net (code "105") (name "Net-(U16-FBG)") (class "Default")
      (node (ref "R70") (pin "1") (pinfunction "1_1") (pintype "passive"))
      (node (ref "U16") (pin "P$11") (pinfunction "FBG_P$11") (pintype "bidirectional"))
    )
    (net (code "106") (name "Net-(U16-MPPT)") (class "Default")
      (node (ref "R63") (pin "1") (pinfunction "1_1") (pintype "passive"))
      (node (ref "R64") (pin "2") (pinfunction "2_2") (pintype "passive"))
      (node (ref "U16") (pin "P$6") (pinfunction "MPPT_P$6") (pintype "bidirectional"))
    )
    (net (code "107") (name "Net-(U16-PROG)") (class "Default")
      (node (ref "R69") (pin "1") (pinfunction "1_1") (pintype "passive"))
      (node (ref "U16") (pin "P$13") (pinfunction "PROG_P$13") (pintype "bidirectional"))
    )
    (net (code "108") (name "Net-(U18-VREF1)") (class "Default")
      (node (ref "R24") (pin "2") (pinfunction "2_2") (pintype "passive"))
      (node (ref "R26") (pin "1") (pinfunction "1_1") (pintype "passive"))
      (node (ref "U18") (pin "P$3") (pinfunction "VREF2_P$3") (pintype "bidirectional"))
      (node (ref "U18") (pin "P$7") (pinfunction "VREF1_P$7") (pintype "bidirectional"))
    )
    (net (code "109") (name "Net-(U19-VREF1)") (class "Default")
      (node (ref "R29") (pin "2") (pinfunction "2_2") (pintype "passive"))
      (node (ref "R30") (pin "1") (pinfunction "1_1") (pintype "passive"))
      (node (ref "U19") (pin "P$3") (pinfunction "VREF2_P$3") (pintype "bidirectional"))
      (node (ref "U19") (pin "P$7") (pinfunction "VREF1_P$7") (pintype "bidirectional"))
    )
    (net (code "110") (name "PANELREF") (class "Default")
      (node (ref "R13") (pin "1") (pinfunction "1_1") (pintype "passive"))
      (node (ref "R14") (pin "2") (pinfunction "2_2") (pintype "passive"))
      (node (ref "U2") (pin "P$6") (pinfunction "VIN3/REF_P$6") (pintype "bidirectional"))
    )
    (net (code "111") (name "SCL") (class "Default")
      (node (ref "R85") (pin "1") (pinfunction "1_1") (pintype "passive"))
      (node (ref "U1") (pin "P$22") (pinfunction "SCL_P$22") (pintype "bidirectional"))
      (node (ref "U2") (pin "P$1") (pinfunction "SCL_P$1") (pintype "bidirectional"))
      (node (ref "V5") (pin "P$1") (pinfunction "P$1_P$1") (pintype "bidirectional"))
    )
    (net (code "112") (name "SDA") (class "Default")
      (node (ref "R86") (pin "1") (pinfunction "1_1") (pintype "passive"))
      (node (ref "U1") (pin "P$23") (pinfunction "SDA_P$23") (pintype "bidirectional"))
      (node (ref "U2") (pin "P$2") (pinfunction "SDA_P$2") (pintype "bidirectional"))
      (node (ref "V6") (pin "P$1") (pinfunction "P$1_P$1") (pintype "bidirectional"))
    )
    (net (code "113") (name "SPF_ST") (class "Default")
      (node (ref "R83") (pin "1") (pinfunction "1_1") (pintype "passive"))
      (node (ref "U1") (pin "P$6") (pinfunction "P02_P$6") (pintype "bidirectional"))
      (node (ref "U3") (pin "P$4") (pinfunction "STAT_P$4") (pintype "bidirectional"))
    )
    (net (code "114") (name "SP_C") (class "Default")
      (node (ref "C3") (pin "1") (pinfunction "P$1_1") (pintype "passive"))
      (node (ref "M1") (pin "P$5") (pinfunction "D_P$5") (pintype "bidirectional"))
      (node (ref "M1") (pin "P$6") (pinfunction "D_P$6") (pintype "bidirectional"))
      (node (ref "M1") (pin "P$7") (pinfunction "D_P$7") (pintype "bidirectional"))
      (node (ref "M1") (pin "P$8") (pinfunction "D_P$8") (pintype "bidirectional"))
      (node (ref "U3") (pin "P$1") (pinfunction "VIN_P$1") (pintype "bidirectional"))
      (node (ref "V13") (pin "P$1") (pinfunction "P$1_P$1") (pintype "bidirectional"))
      (node (ref "V14") (pin "P$1") (pinfunction "P$1_P$1") (pintype "bidirectional"))
      (node (ref "V15") (pin "P$1") (pinfunction "P$1_P$1") (pintype "bidirectional"))
      (node (ref "V16") (pin "P$1") (pinfunction "P$1_P$1") (pintype "bidirectional"))
      (node (ref "V17") (pin "P$1") (pinfunction "P$1_P$1") (pintype "bidirectional"))
      (node (ref "V18") (pin "P$1") (pinfunction "P$1_P$1") (pintype "bidirectional"))
    )
    (net (code "115") (name "SP_OUT") (class "Default")
      (node (ref "C17") (pin "1") (pinfunction "P$1_1") (pintype "passive"))
      (node (ref "C18") (pin "1") (pinfunction "P$1_1") (pintype "passive"))
      (node (ref "C25") (pin "2") (pinfunction "P$2_2") (pintype "passive"))
      (node (ref "C32") (pin "2") (pinfunction "P$2_2") (pintype "passive"))
      (node (ref "C4") (pin "1") (pinfunction "P$1_1") (pintype "passive"))
      (node (ref "C5") (pin "1") (pinfunction "P$1_1") (pintype "passive"))
      (node (ref "C6") (pin "1") (pinfunction "P$1_1") (pintype "passive"))
      (node (ref "D1") (pin "C") (pinfunction "C_C") (pintype "bidirectional"))
      (node (ref "M1") (pin "P$1") (pinfunction "S_P$1") (pintype "bidirectional"))
      (node (ref "M1") (pin "P$2") (pinfunction "S_P$2") (pintype "bidirectional"))
      (node (ref "M1") (pin "P$3") (pinfunction "S_P$3") (pintype "bidirectional"))
      (node (ref "R1") (pin "1") (pinfunction "1_1") (pintype "passive"))
      (node (ref "R10") (pin "2") (pinfunction "2_2") (pintype "passive"))
      (node (ref "R13") (pin "2") (pinfunction "2_2") (pintype "passive"))
      (node (ref "R15") (pin "1") (pinfunction "1_1") (pintype "passive"))
      (node (ref "R27") (pin "2") (pinfunction "2_2") (pintype "passive"))
      (node (ref "R45") (pin "2") (pinfunction "2_2") (pintype "passive"))
      (node (ref "R63") (pin "2") (pinfunction "2_2") (pintype "passive"))
      (node (ref "U10") (pin "P$5") (pinfunction "~{SHDN}_P$5") (pintype "bidirectional"))
      (node (ref "U10") (pin "P$8") (pinfunction "IN_P$8") (pintype "bidirectional"))
      (node (ref "U11") (pin "P$5") (pinfunction "~{SHDN}_P$5") (pintype "bidirectional"))
      (node (ref "U11") (pin "P$8") (pinfunction "IN_P$8") (pintype "bidirectional"))
      (node (ref "U14") (pin "P$3") (pinfunction "IN_P$3") (pintype "bidirectional"))
      (node (ref "U16") (pin "P$3") (pinfunction "IN_P$3") (pintype "bidirectional"))
      (node (ref "U3") (pin "P$6") (pinfunction "SNS_P$6") (pintype "bidirectional"))
      (node (ref "U4") (pin "P$3") (pinfunction "IN_P$3") (pintype "bidirectional"))
      (node (ref "U5") (pin "P$3") (pinfunction "IN_P$3") (pintype "bidirectional"))
    )
    (net (code "116") (name "UMB_CHG") (class "Default")
      (node (ref "D1") (pin "A") (pinfunction "A_A") (pintype "bidirectional"))
      (node (ref "V19") (pin "P$1") (pinfunction "P$1_P$1") (pintype "bidirectional"))
    )
    (net (code "117") (name "~{BATT_INT}") (class "Default")
      (node (ref "R84") (pin "1") (pinfunction "1_1") (pintype "passive"))
      (node (ref "U1") (pin "P$1") (pinfunction "~{INT}_P$1") (pintype "bidirectional"))
    )
  )
)
